# module_bga.net
KiCad netlist of a schematic drawn in EAGLE
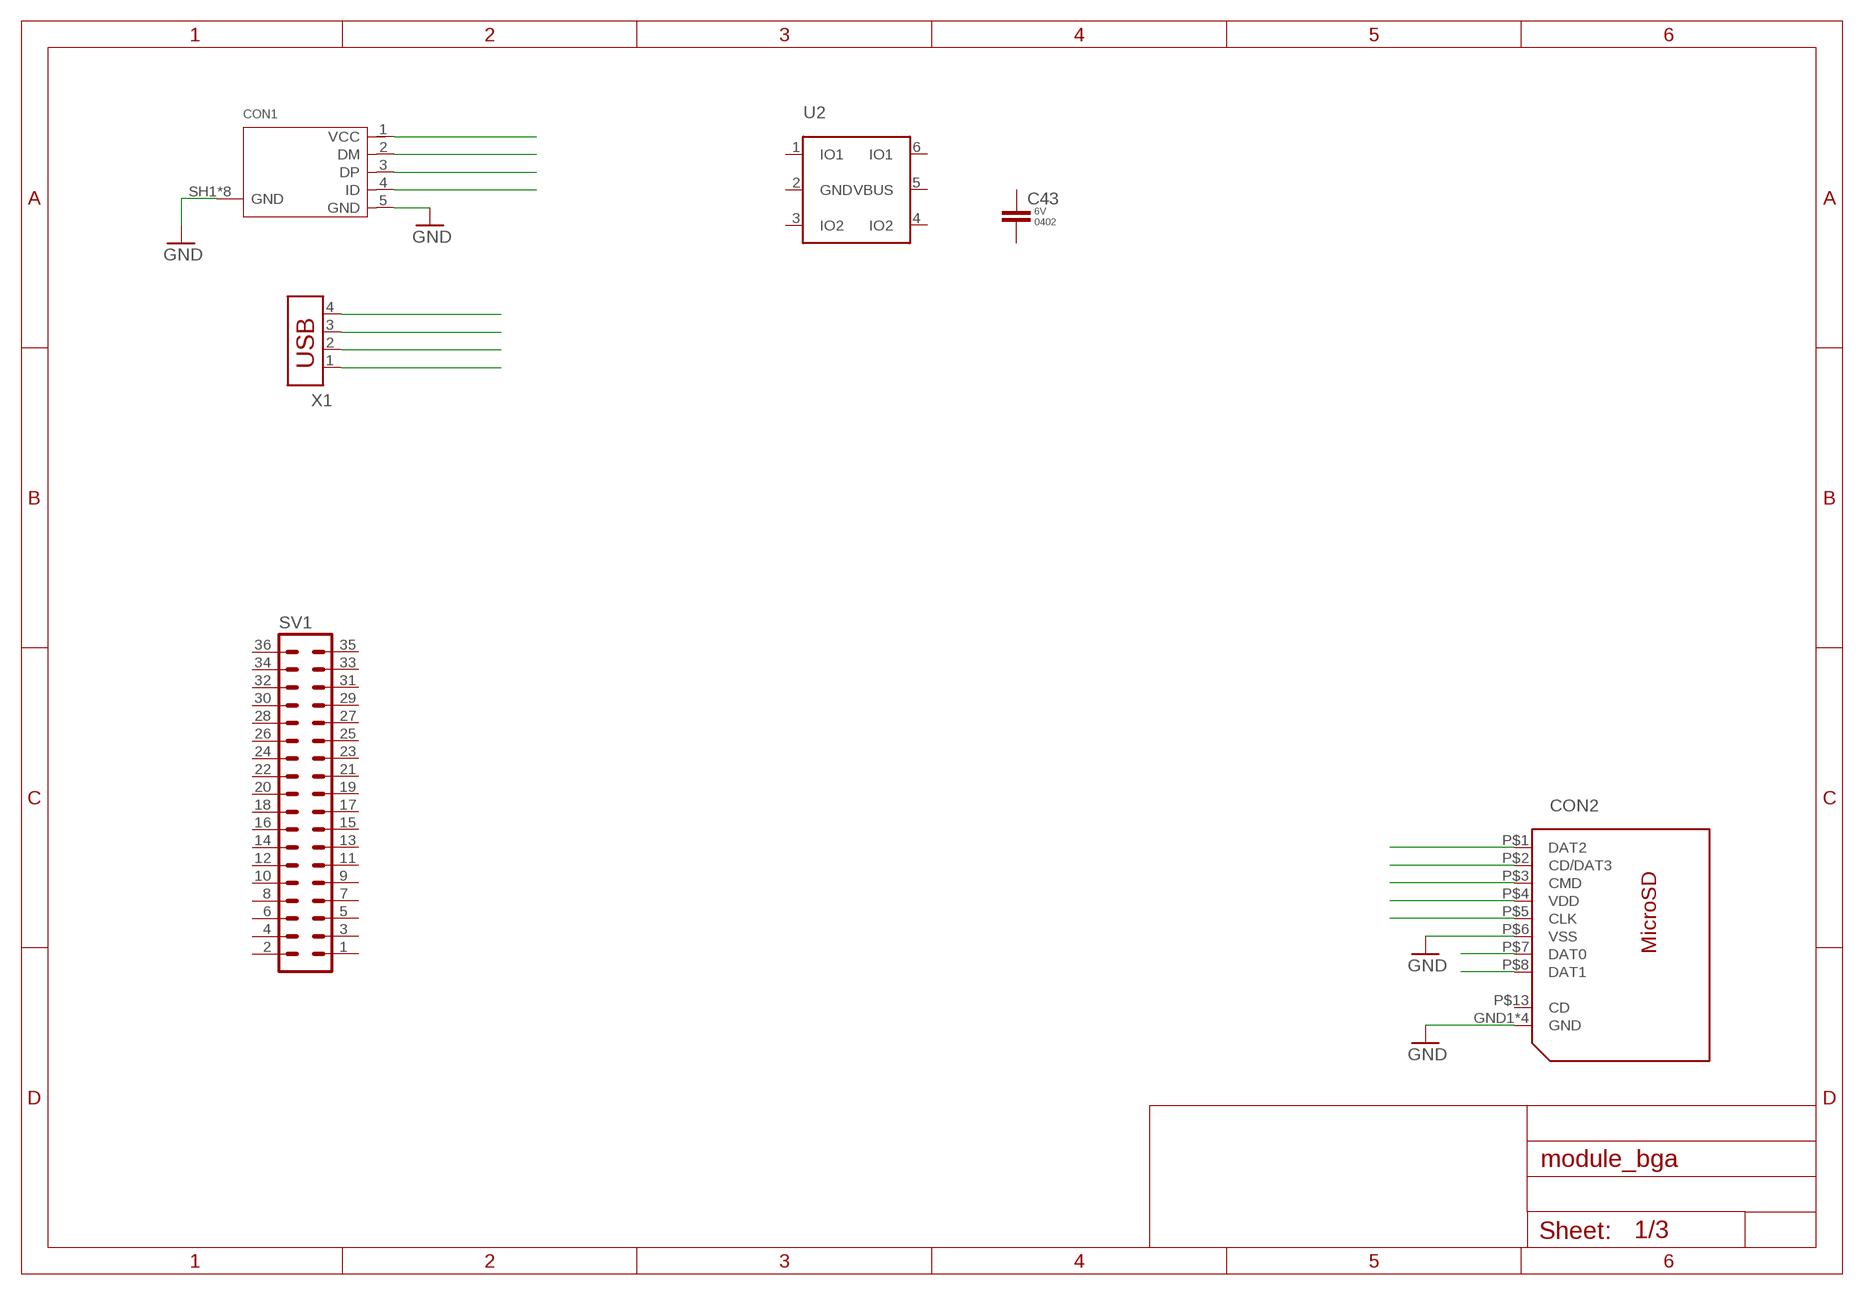
[diagram p0: schematic, sheet 1]
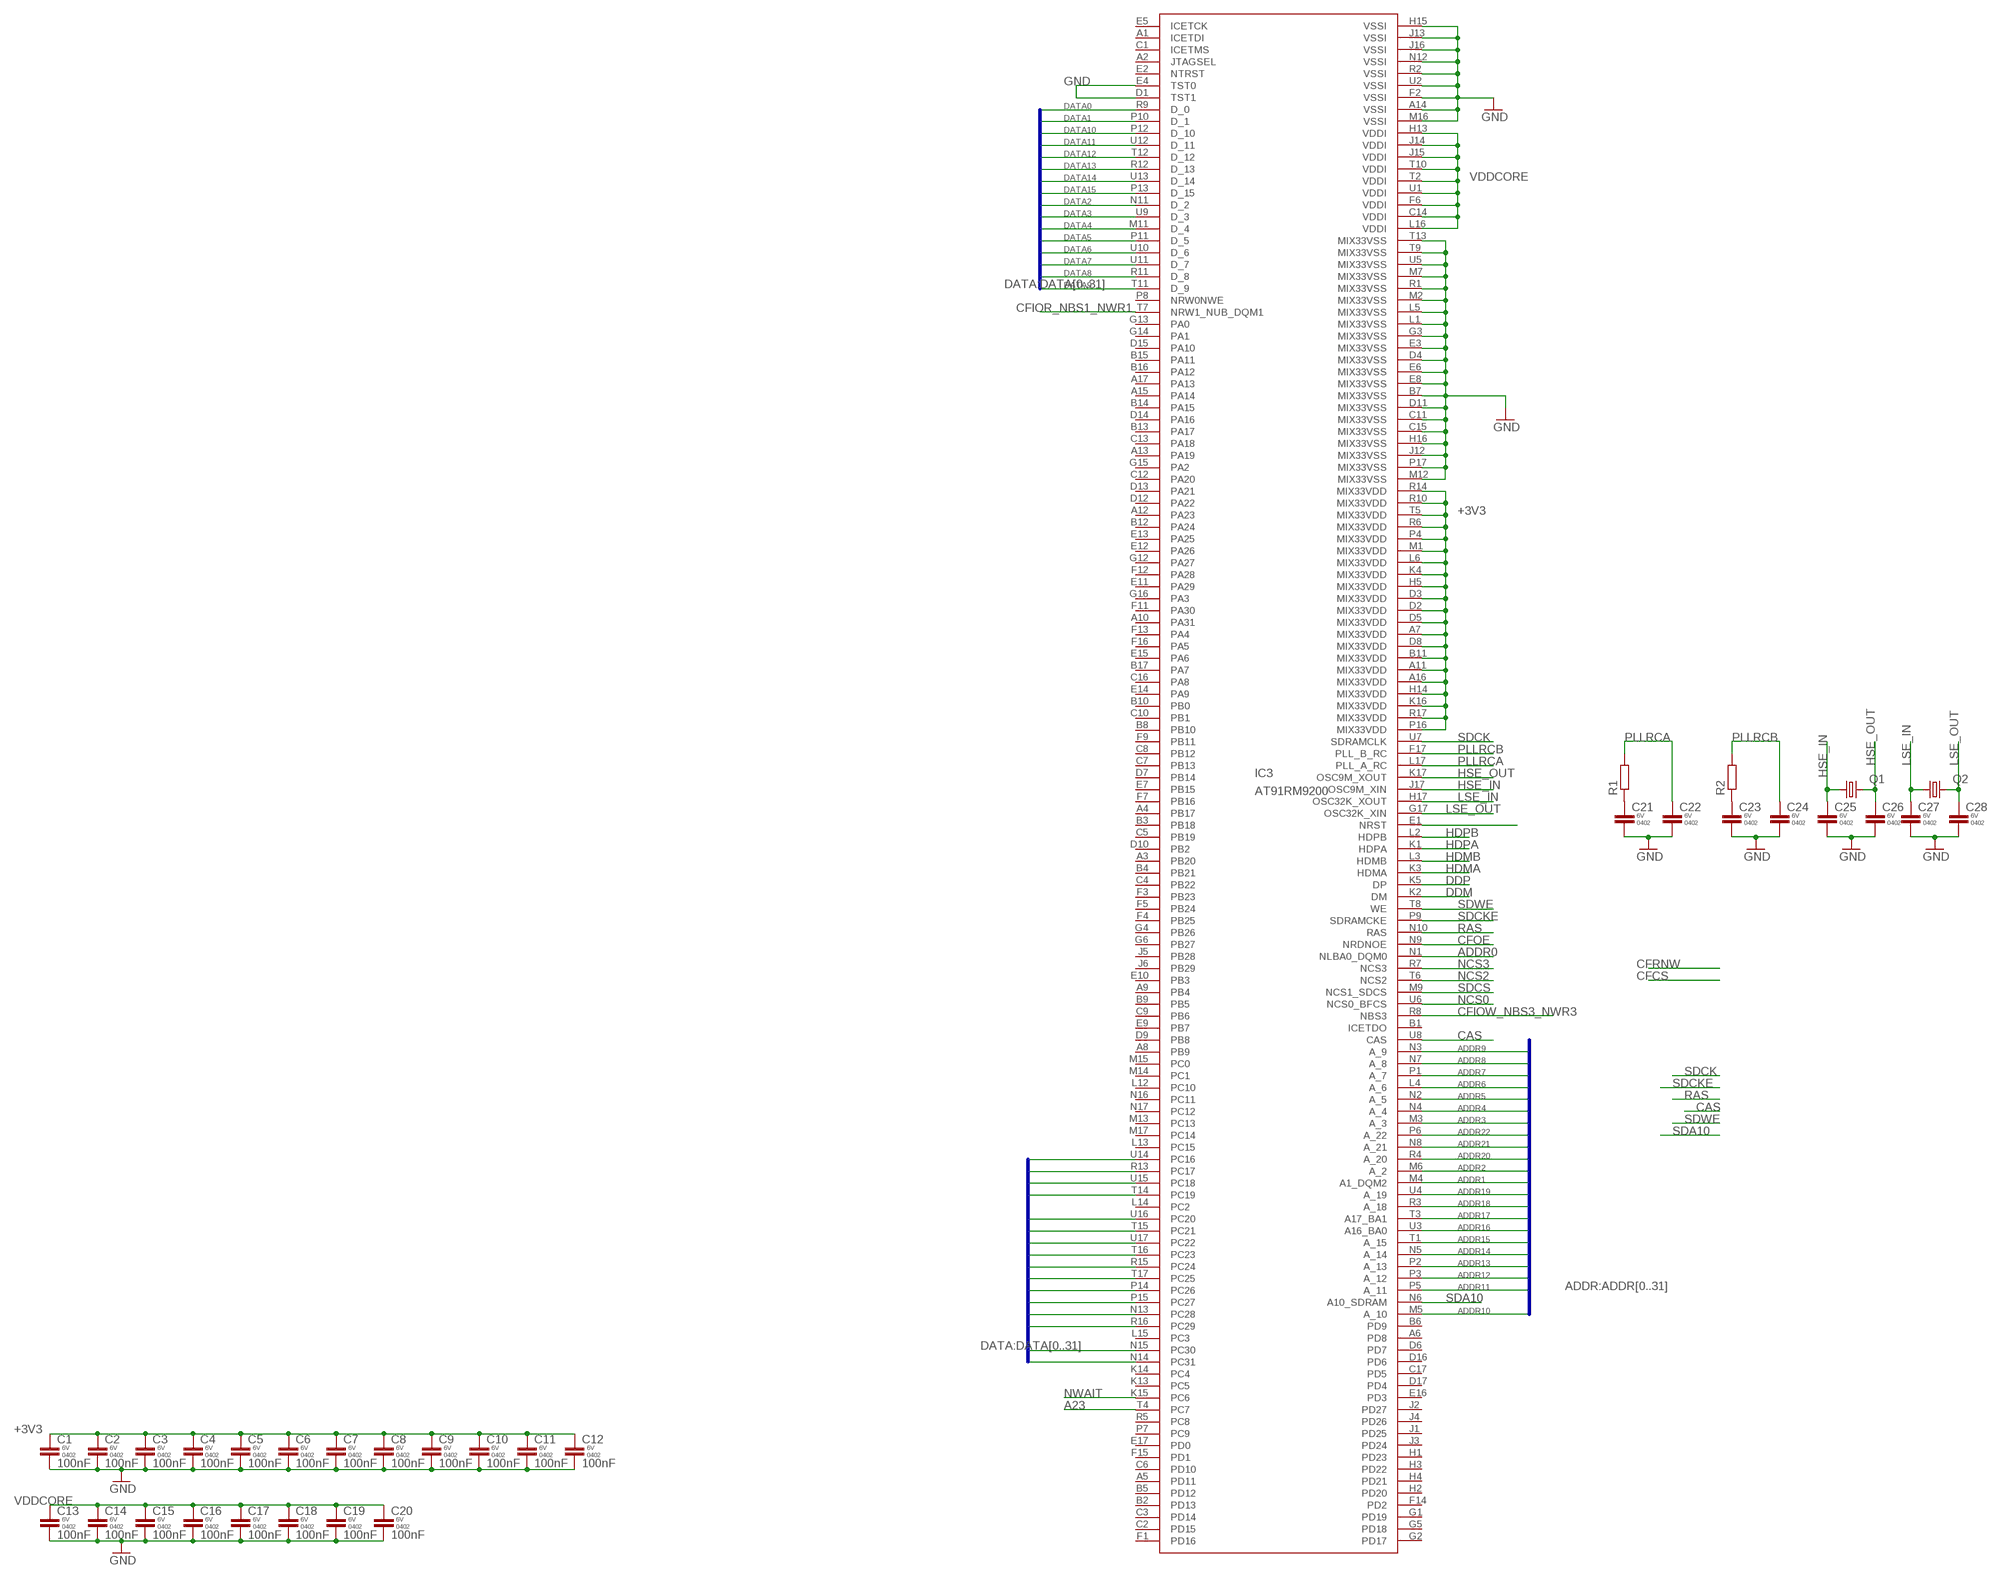
[diagram p1: schematic, sheet 2]
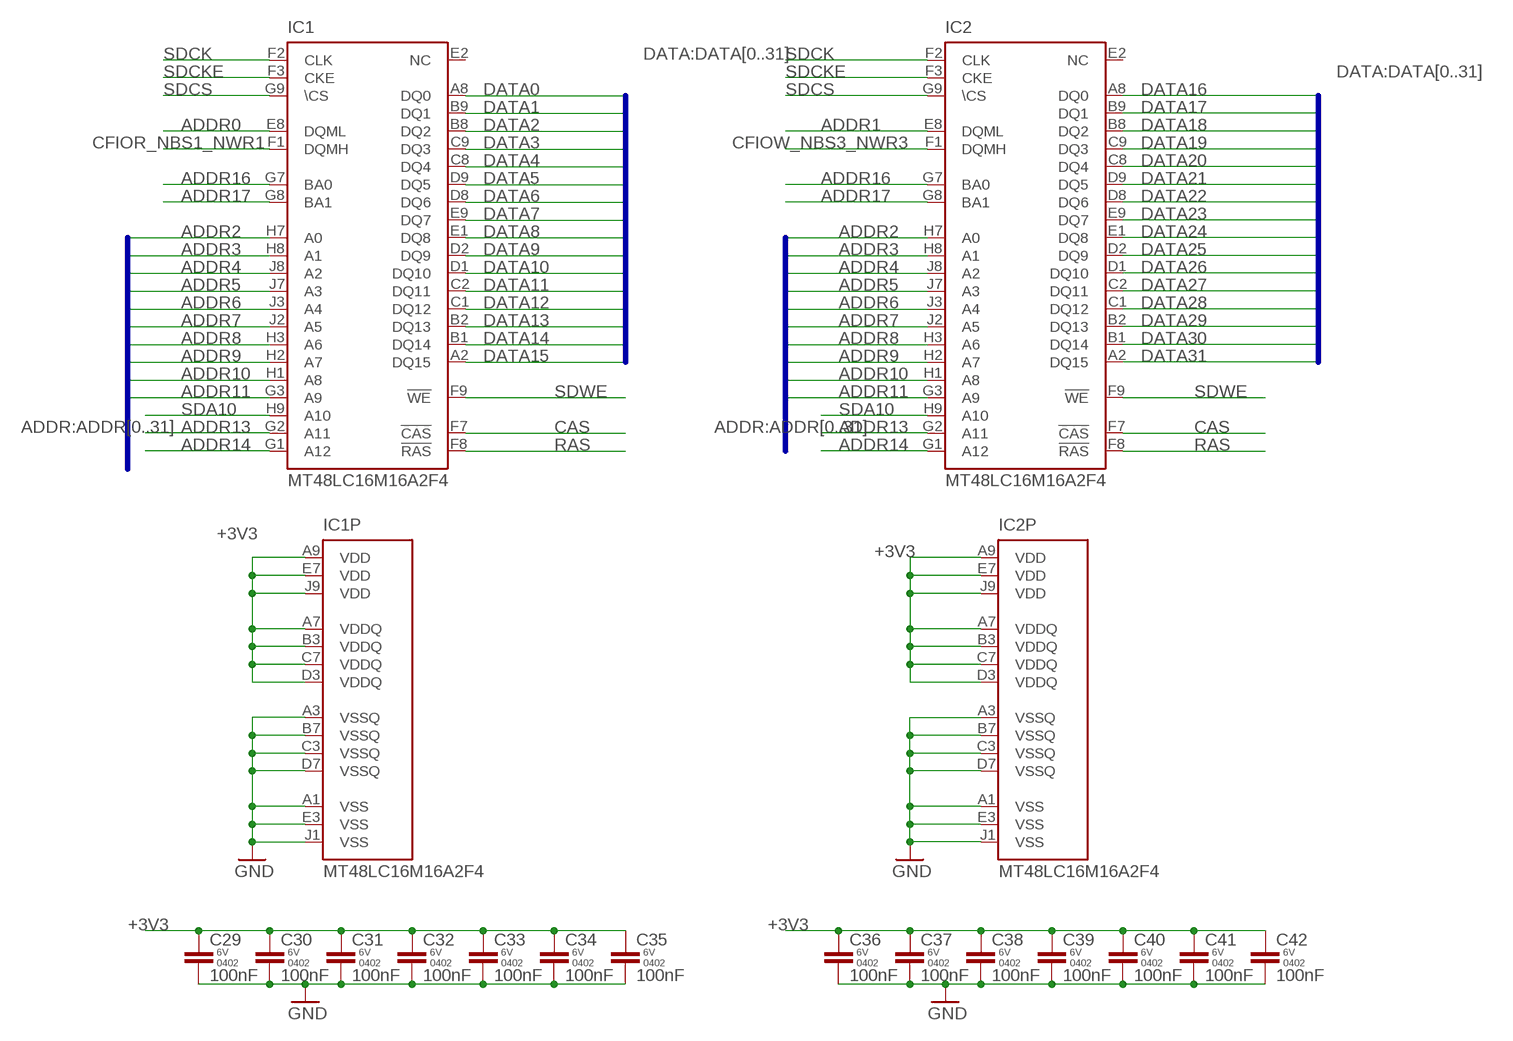
[diagram p2: schematic, sheet 3]

(export (version "E")
  (design (tool "Eeschema 10.0.6"))
  (components
    (comp (ref "C43")
      (value "CAP-0402")
      (footprint "eagle-import:C0402K")
      (fields (field (name "RATING") "6V") (field (name "PACKAGE") "0402"))
      (libsource (lib "eagle-import") (part "CAP-0402"))
    )
    (comp (ref "CON1")
      (value "10118194-0001LF")
      (footprint "eagle-import:10118194")
      (libsource (lib "eagle-import") (part "10118194-0001LF"))
    )
    (comp (ref "CON2")
      (value "112J-TXAR")
      (footprint "eagle-import:112J")
      (libsource (lib "eagle-import") (part "112J-TXAR"))
    )
    (comp (ref "SV1")
      (value "MA18-2")
      (footprint "eagle-import:MA18-2")
      (libsource (lib "eagle-import") (part "MA18-2"))
    )
    (comp (ref "U2")
      (value "USBLC6-2SC6")
      (footprint "eagle-import:SOT95P280X110-6")
      (libsource (lib "eagle-import") (part "USBLC6-2SC6"))
    )
    (comp (ref "X1")
      (value "USB-787616")
      (footprint "eagle-import:USB")
      (libsource (lib "eagle-import") (part "USB-787616"))
    )
    (comp (ref "C1")
      (value "100nF")
      (footprint "eagle-import:C0402K")
      (fields (field (name "RATING") "6V") (field (name "PACKAGE") "0402"))
      (libsource (lib "eagle-import") (part "CAP-0402"))
    )
    (comp (ref "C2")
      (value "100nF")
      (footprint "eagle-import:C0402K")
      (fields (field (name "RATING") "6V") (field (name "PACKAGE") "0402"))
      (libsource (lib "eagle-import") (part "CAP-0402"))
    )
    (comp (ref "C3")
      (value "100nF")
      (footprint "eagle-import:C0402K")
      (fields (field (name "RATING") "6V") (field (name "PACKAGE") "0402"))
      (libsource (lib "eagle-import") (part "CAP-0402"))
    )
    (comp (ref "C4")
      (value "100nF")
      (footprint "eagle-import:C0402K")
      (fields (field (name "RATING") "6V") (field (name "PACKAGE") "0402"))
      (libsource (lib "eagle-import") (part "CAP-0402"))
    )
    (comp (ref "C5")
      (value "100nF")
      (footprint "eagle-import:C0402K")
      (fields (field (name "RATING") "6V") (field (name "PACKAGE") "0402"))
      (libsource (lib "eagle-import") (part "CAP-0402"))
    )
    (comp (ref "C6")
      (value "100nF")
      (footprint "eagle-import:C0402K")
      (fields (field (name "RATING") "6V") (field (name "PACKAGE") "0402"))
      (libsource (lib "eagle-import") (part "CAP-0402"))
    )
    (comp (ref "C7")
      (value "100nF")
      (footprint "eagle-import:C0402K")
      (fields (field (name "RATING") "6V") (field (name "PACKAGE") "0402"))
      (libsource (lib "eagle-import") (part "CAP-0402"))
    )
    (comp (ref "C8")
      (value "100nF")
      (footprint "eagle-import:C0402K")
      (fields (field (name "RATING") "6V") (field (name "PACKAGE") "0402"))
      (libsource (lib "eagle-import") (part "CAP-0402"))
    )
    (comp (ref "C9")
      (value "100nF")
      (footprint "eagle-import:C0402K")
      (fields (field (name "RATING") "6V") (field (name "PACKAGE") "0402"))
      (libsource (lib "eagle-import") (part "CAP-0402"))
    )
    (comp (ref "C10")
      (value "100nF")
      (footprint "eagle-import:C0402K")
      (fields (field (name "RATING") "6V") (field (name "PACKAGE") "0402"))
      (libsource (lib "eagle-import") (part "CAP-0402"))
    )
    (comp (ref "C11")
      (value "100nF")
      (footprint "eagle-import:C0402K")
      (fields (field (name "RATING") "6V") (field (name "PACKAGE") "0402"))
      (libsource (lib "eagle-import") (part "CAP-0402"))
    )
    (comp (ref "C12")
      (value "100nF")
      (footprint "eagle-import:C0402K")
      (fields (field (name "RATING") "6V") (field (name "PACKAGE") "0402"))
      (libsource (lib "eagle-import") (part "CAP-0402"))
    )
    (comp (ref "C13")
      (value "100nF")
      (footprint "eagle-import:C0402K")
      (fields (field (name "RATING") "6V") (field (name "PACKAGE") "0402"))
      (libsource (lib "eagle-import") (part "CAP-0402"))
    )
    (comp (ref "C14")
      (value "100nF")
      (footprint "eagle-import:C0402K")
      (fields (field (name "RATING") "6V") (field (name "PACKAGE") "0402"))
      (libsource (lib "eagle-import") (part "CAP-0402"))
    )
    (comp (ref "C15")
      (value "100nF")
      (footprint "eagle-import:C0402K")
      (fields (field (name "RATING") "6V") (field (name "PACKAGE") "0402"))
      (libsource (lib "eagle-import") (part "CAP-0402"))
    )
    (comp (ref "C16")
      (value "100nF")
      (footprint "eagle-import:C0402K")
      (fields (field (name "RATING") "6V") (field (name "PACKAGE") "0402"))
      (libsource (lib "eagle-import") (part "CAP-0402"))
    )
    (comp (ref "C17")
      (value "100nF")
      (footprint "eagle-import:C0402K")
      (fields (field (name "RATING") "6V") (field (name "PACKAGE") "0402"))
      (libsource (lib "eagle-import") (part "CAP-0402"))
    )
    (comp (ref "C18")
      (value "100nF")
      (footprint "eagle-import:C0402K")
      (fields (field (name "RATING") "6V") (field (name "PACKAGE") "0402"))
      (libsource (lib "eagle-import") (part "CAP-0402"))
    )
    (comp (ref "C19")
      (value "100nF")
      (footprint "eagle-import:C0402K")
      (fields (field (name "RATING") "6V") (field (name "PACKAGE") "0402"))
      (libsource (lib "eagle-import") (part "CAP-0402"))
    )
    (comp (ref "C20")
      (value "100nF")
      (footprint "eagle-import:C0402K")
      (fields (field (name "RATING") "6V") (field (name "PACKAGE") "0402"))
      (libsource (lib "eagle-import") (part "CAP-0402"))
    )
    (comp (ref "C21")
      (value "CAP-0402")
      (footprint "eagle-import:C0402K")
      (fields (field (name "RATING") "6V") (field (name "PACKAGE") "0402"))
      (libsource (lib "eagle-import") (part "CAP-0402"))
    )
    (comp (ref "C22")
      (value "CAP-0402")
      (footprint "eagle-import:C0402K")
      (fields (field (name "RATING") "6V") (field (name "PACKAGE") "0402"))
      (libsource (lib "eagle-import") (part "CAP-0402"))
    )
    (comp (ref "C23")
      (value "CAP-0402")
      (footprint "eagle-import:C0402K")
      (fields (field (name "RATING") "6V") (field (name "PACKAGE") "0402"))
      (libsource (lib "eagle-import") (part "CAP-0402"))
    )
    (comp (ref "C24")
      (value "CAP-0402")
      (footprint "eagle-import:C0402K")
      (fields (field (name "RATING") "6V") (field (name "PACKAGE") "0402"))
      (libsource (lib "eagle-import") (part "CAP-0402"))
    )
    (comp (ref "C25")
      (value "CAP-0402")
      (footprint "eagle-import:C0402K")
      (fields (field (name "RATING") "6V") (field (name "PACKAGE") "0402"))
      (libsource (lib "eagle-import") (part "CAP-0402"))
    )
    (comp (ref "C26")
      (value "CAP-0402")
      (footprint "eagle-import:C0402K")
      (fields (field (name "RATING") "6V") (field (name "PACKAGE") "0402"))
      (libsource (lib "eagle-import") (part "CAP-0402"))
    )
    (comp (ref "C27")
      (value "CAP-0402")
      (footprint "eagle-import:C0402K")
      (fields (field (name "RATING") "6V") (field (name "PACKAGE") "0402"))
      (libsource (lib "eagle-import") (part "CAP-0402"))
    )
    (comp (ref "C28")
      (value "CAP-0402")
      (footprint "eagle-import:C0402K")
      (fields (field (name "RATING") "6V") (field (name "PACKAGE") "0402"))
      (libsource (lib "eagle-import") (part "CAP-0402"))
    )
    (comp (ref "IC3")
      (value "AT91RM9200")
      (footprint "eagle-import:LFBGA256_A_291X326")
      (fields (field (name "MPN") "AT91RM9200-EK"))
      (libsource (lib "eagle-import") (part "AT91RM9200"))
    )
    (comp (ref "Q1")
      (value "KX-7")
      (footprint "eagle-import:3.2X2.5_KX-7")
      (libsource (lib "eagle-import") (part "KX-7"))
    )
    (comp (ref "Q2")
      (value "KX-327-NHF")
      (footprint "eagle-import:3.2X1.5")
      (libsource (lib "eagle-import") (part "KX-327-NHF"))
    )
    (comp (ref "R1")
      (value "R-EU_R0402")
      (footprint "eagle-import:R0402")
      (libsource (lib "eagle-import") (part "R-EU_R0402"))
    )
    (comp (ref "R2")
      (value "R-EU_R0402")
      (footprint "eagle-import:R0402")
      (libsource (lib "eagle-import") (part "R-EU_R0402"))
    )
    (comp (ref "C29")
      (value "100nF")
      (footprint "eagle-import:C0402K")
      (fields (field (name "RATING") "6V") (field (name "PACKAGE") "0402"))
      (libsource (lib "eagle-import") (part "CAP-0402"))
    )
    (comp (ref "C30")
      (value "100nF")
      (footprint "eagle-import:C0402K")
      (fields (field (name "RATING") "6V") (field (name "PACKAGE") "0402"))
      (libsource (lib "eagle-import") (part "CAP-0402"))
    )
    (comp (ref "C31")
      (value "100nF")
      (footprint "eagle-import:C0402K")
      (fields (field (name "RATING") "6V") (field (name "PACKAGE") "0402"))
      (libsource (lib "eagle-import") (part "CAP-0402"))
    )
    (comp (ref "C32")
      (value "100nF")
      (footprint "eagle-import:C0402K")
      (fields (field (name "RATING") "6V") (field (name "PACKAGE") "0402"))
      (libsource (lib "eagle-import") (part "CAP-0402"))
    )
    (comp (ref "C33")
      (value "100nF")
      (footprint "eagle-import:C0402K")
      (fields (field (name "RATING") "6V") (field (name "PACKAGE") "0402"))
      (libsource (lib "eagle-import") (part "CAP-0402"))
    )
    (comp (ref "C34")
      (value "100nF")
      (footprint "eagle-import:C0402K")
      (fields (field (name "RATING") "6V") (field (name "PACKAGE") "0402"))
      (libsource (lib "eagle-import") (part "CAP-0402"))
    )
    (comp (ref "C35")
      (value "100nF")
      (footprint "eagle-import:C0402K")
      (fields (field (name "RATING") "6V") (field (name "PACKAGE") "0402"))
      (libsource (lib "eagle-import") (part "CAP-0402"))
    )
    (comp (ref "C36")
      (value "100nF")
      (footprint "eagle-import:C0402K")
      (fields (field (name "RATING") "6V") (field (name "PACKAGE") "0402"))
      (libsource (lib "eagle-import") (part "CAP-0402"))
    )
    (comp (ref "C37")
      (value "100nF")
      (footprint "eagle-import:C0402K")
      (fields (field (name "RATING") "6V") (field (name "PACKAGE") "0402"))
      (libsource (lib "eagle-import") (part "CAP-0402"))
    )
    (comp (ref "C38")
      (value "100nF")
      (footprint "eagle-import:C0402K")
      (fields (field (name "RATING") "6V") (field (name "PACKAGE") "0402"))
      (libsource (lib "eagle-import") (part "CAP-0402"))
    )
    (comp (ref "C39")
      (value "100nF")
      (footprint "eagle-import:C0402K")
      (fields (field (name "RATING") "6V") (field (name "PACKAGE") "0402"))
      (libsource (lib "eagle-import") (part "CAP-0402"))
    )
    (comp (ref "C40")
      (value "100nF")
      (footprint "eagle-import:C0402K")
      (fields (field (name "RATING") "6V") (field (name "PACKAGE") "0402"))
      (libsource (lib "eagle-import") (part "CAP-0402"))
    )
    (comp (ref "C41")
      (value "100nF")
      (footprint "eagle-import:C0402K")
      (fields (field (name "RATING") "6V") (field (name "PACKAGE") "0402"))
      (libsource (lib "eagle-import") (part "CAP-0402"))
    )
    (comp (ref "C42")
      (value "100nF")
      (footprint "eagle-import:C0402K")
      (fields (field (name "RATING") "6V") (field (name "PACKAGE") "0402"))
      (libsource (lib "eagle-import") (part "CAP-0402"))
    )
    (comp (ref "IC1")
      (value "MT48LC16M16A2F4")
      (footprint "eagle-import:BGA81C80P9X9_800X800X100")
      (libsource (lib "eagle-import") (part "MT48LC16M16A2F4"))
    )
    (comp (ref "IC2")
      (value "MT48LC16M16A2F4")
      (footprint "eagle-import:BGA81C80P9X9_800X800X100")
      (libsource (lib "eagle-import") (part "MT48LC16M16A2F4"))
    )
  )
  (nets
    (net (code "129") (name "+3V3") (class "Default")
      (node (ref "C1") (pin "1") (pinfunction "1_1") (pintype "passive"))
      (node (ref "C10") (pin "1") (pinfunction "1_1") (pintype "passive"))
      (node (ref "C11") (pin "1") (pinfunction "1_1") (pintype "passive"))
      (node (ref "C12") (pin "1") (pinfunction "1_1") (pintype "passive"))
      (node (ref "C2") (pin "1") (pinfunction "1_1") (pintype "passive"))
      (node (ref "C29") (pin "1") (pinfunction "1_1") (pintype "passive"))
      (node (ref "C3") (pin "1") (pinfunction "1_1") (pintype "passive"))
      (node (ref "C30") (pin "1") (pinfunction "1_1") (pintype "passive"))
      (node (ref "C31") (pin "1") (pinfunction "1_1") (pintype "passive"))
      (node (ref "C32") (pin "1") (pinfunction "1_1") (pintype "passive"))
      (node (ref "C33") (pin "1") (pinfunction "1_1") (pintype "passive"))
      (node (ref "C34") (pin "1") (pinfunction "1_1") (pintype "passive"))
      (node (ref "C35") (pin "1") (pinfunction "1_1") (pintype "passive"))
      (node (ref "C36") (pin "1") (pinfunction "1_1") (pintype "passive"))
      (node (ref "C37") (pin "1") (pinfunction "1_1") (pintype "passive"))
      (node (ref "C38") (pin "1") (pinfunction "1_1") (pintype "passive"))
      (node (ref "C39") (pin "1") (pinfunction "1_1") (pintype "passive"))
      (node (ref "C4") (pin "1") (pinfunction "1_1") (pintype "passive"))
      (node (ref "C40") (pin "1") (pinfunction "1_1") (pintype "passive"))
      (node (ref "C41") (pin "1") (pinfunction "1_1") (pintype "passive"))
      (node (ref "C42") (pin "1") (pinfunction "1_1") (pintype "passive"))
      (node (ref "C5") (pin "1") (pinfunction "1_1") (pintype "passive"))
      (node (ref "C6") (pin "1") (pinfunction "1_1") (pintype "passive"))
      (node (ref "C7") (pin "1") (pinfunction "1_1") (pintype "passive"))
      (node (ref "C8") (pin "1") (pinfunction "1_1") (pintype "passive"))
      (node (ref "C9") (pin "1") (pinfunction "1_1") (pintype "passive"))
      (node (ref "IC1") (pin "A7") (pinfunction "VDDQ_A7") (pintype "power_in"))
      (node (ref "IC1") (pin "A9") (pinfunction "VDD_A9") (pintype "power_in"))
      (node (ref "IC1") (pin "B3") (pinfunction "VDDQ_B3") (pintype "power_in"))
      (node (ref "IC1") (pin "C7") (pinfunction "VDDQ_C7") (pintype "power_in"))
      (node (ref "IC1") (pin "D3") (pinfunction "VDDQ_D3") (pintype "power_in"))
      (node (ref "IC1") (pin "E7") (pinfunction "VDD_E7") (pintype "power_in"))
      (node (ref "IC1") (pin "J9") (pinfunction "VDD_J9") (pintype "power_in"))
      (node (ref "IC2") (pin "A7") (pinfunction "VDDQ_A7") (pintype "power_in"))
      (node (ref "IC2") (pin "A9") (pinfunction "VDD_A9") (pintype "power_in"))
      (node (ref "IC2") (pin "B3") (pinfunction "VDDQ_B3") (pintype "power_in"))
      (node (ref "IC2") (pin "C7") (pinfunction "VDDQ_C7") (pintype "power_in"))
      (node (ref "IC2") (pin "D3") (pinfunction "VDDQ_D3") (pintype "power_in"))
      (node (ref "IC2") (pin "E7") (pinfunction "VDD_E7") (pintype "power_in"))
      (node (ref "IC2") (pin "J9") (pinfunction "VDD_J9") (pintype "power_in"))
      (node (ref "IC3") (pin "A11") (pinfunction "MIX33VDD_A11") (pintype "power_in"))
      (node (ref "IC3") (pin "A16") (pinfunction "MIX33VDD_A16") (pintype "power_in"))
      (node (ref "IC3") (pin "A7") (pinfunction "MIX33VDD_A7") (pintype "power_in"))
      (node (ref "IC3") (pin "B11") (pinfunction "MIX33VDD_B11") (pintype "power_in"))
      (node (ref "IC3") (pin "D2") (pinfunction "MIX33VDD_D2") (pintype "power_in"))
      (node (ref "IC3") (pin "D3") (pinfunction "MIX33VDD_D3") (pintype "power_in"))
      (node (ref "IC3") (pin "D5") (pinfunction "MIX33VDD_D5") (pintype "power_in"))
      (node (ref "IC3") (pin "D8") (pinfunction "MIX33VDD_D8") (pintype "power_in"))
      (node (ref "IC3") (pin "H14") (pinfunction "MIX33VDD_H14") (pintype "power_in"))
      (node (ref "IC3") (pin "H5") (pinfunction "MIX33VDD_H5") (pintype "power_in"))
      (node (ref "IC3") (pin "K16") (pinfunction "MIX33VDD_K16") (pintype "power_in"))
      (node (ref "IC3") (pin "K4") (pinfunction "MIX33VDD_K4") (pintype "power_in"))
      (node (ref "IC3") (pin "L6") (pinfunction "MIX33VDD_L6") (pintype "power_in"))
      (node (ref "IC3") (pin "M1") (pinfunction "MIX33VDD_M1") (pintype "power_in"))
      (node (ref "IC3") (pin "P16") (pinfunction "MIX33VDD_P16") (pintype "power_in"))
      (node (ref "IC3") (pin "P4") (pinfunction "MIX33VDD_P4") (pintype "power_in"))
      (node (ref "IC3") (pin "R10") (pinfunction "MIX33VDD_R10") (pintype "power_in"))
      (node (ref "IC3") (pin "R14") (pinfunction "MIX33VDD_R14") (pintype "power_in"))
      (node (ref "IC3") (pin "R17") (pinfunction "MIX33VDD_R17") (pintype "power_in"))
      (node (ref "IC3") (pin "R6") (pinfunction "MIX33VDD_R6") (pintype "power_in"))
      (node (ref "IC3") (pin "T5") (pinfunction "MIX33VDD_T5") (pintype "power_in"))
    )
    (net (code "134") (name "A23") (class "Default")
      (node (ref "IC3") (pin "T4") (pinfunction "PC7_T4") (pintype "bidirectional"))
    )
    (net (code "135") (name "ADDR0") (class "Default")
      (node (ref "IC1") (pin "E8") (pinfunction "DQML_E8") (pintype "input"))
      (node (ref "IC3") (pin "N1") (pinfunction "NLBA0_DQM0_N1") (pintype "output"))
    )
    (net (code "136") (name "ADDR1") (class "Default")
      (node (ref "IC2") (pin "E8") (pinfunction "DQML_E8") (pintype "input"))
      (node (ref "IC3") (pin "M4") (pinfunction "A1_DQM2_M4") (pintype "output"))
    )
    (net (code "137") (name "ADDR2") (class "Default")
      (node (ref "IC1") (pin "H7") (pinfunction "A0_H7") (pintype "input"))
      (node (ref "IC2") (pin "H7") (pinfunction "A0_H7") (pintype "input"))
      (node (ref "IC3") (pin "M6") (pinfunction "A_2_M6") (pintype "output"))
    )
    (net (code "138") (name "ADDR3") (class "Default")
      (node (ref "IC1") (pin "H8") (pinfunction "A1_H8") (pintype "input"))
      (node (ref "IC2") (pin "H8") (pinfunction "A1_H8") (pintype "input"))
      (node (ref "IC3") (pin "M3") (pinfunction "A_3_M3") (pintype "output"))
    )
    (net (code "139") (name "ADDR4") (class "Default")
      (node (ref "IC1") (pin "J8") (pinfunction "A2_J8") (pintype "input"))
      (node (ref "IC2") (pin "J8") (pinfunction "A2_J8") (pintype "input"))
      (node (ref "IC3") (pin "N4") (pinfunction "A_4_N4") (pintype "output"))
    )
    (net (code "140") (name "ADDR5") (class "Default")
      (node (ref "IC1") (pin "J7") (pinfunction "A3_J7") (pintype "input"))
      (node (ref "IC2") (pin "J7") (pinfunction "A3_J7") (pintype "input"))
      (node (ref "IC3") (pin "N2") (pinfunction "A_5_N2") (pintype "output"))
    )
    (net (code "141") (name "ADDR6") (class "Default")
      (node (ref "IC1") (pin "J3") (pinfunction "A4_J3") (pintype "input"))
      (node (ref "IC2") (pin "J3") (pinfunction "A4_J3") (pintype "input"))
      (node (ref "IC3") (pin "L4") (pinfunction "A_6_L4") (pintype "output"))
    )
    (net (code "142") (name "ADDR7") (class "Default")
      (node (ref "IC1") (pin "J2") (pinfunction "A5_J2") (pintype "input"))
      (node (ref "IC2") (pin "J2") (pinfunction "A5_J2") (pintype "input"))
      (node (ref "IC3") (pin "P1") (pinfunction "A_7_P1") (pintype "output"))
    )
    (net (code "143") (name "ADDR8") (class "Default")
      (node (ref "IC1") (pin "H3") (pinfunction "A6_H3") (pintype "input"))
      (node (ref "IC2") (pin "H3") (pinfunction "A6_H3") (pintype "input"))
      (node (ref "IC3") (pin "N7") (pinfunction "A_8_N7") (pintype "output"))
    )
    (net (code "144") (name "ADDR9") (class "Default")
      (node (ref "IC1") (pin "H2") (pinfunction "A7_H2") (pintype "input"))
      (node (ref "IC2") (pin "H2") (pinfunction "A7_H2") (pintype "input"))
      (node (ref "IC3") (pin "N3") (pinfunction "A_9_N3") (pintype "output"))
    )
    (net (code "145") (name "ADDR10") (class "Default")
      (node (ref "IC1") (pin "H1") (pinfunction "A8_H1") (pintype "input"))
      (node (ref "IC2") (pin "H1") (pinfunction "A8_H1") (pintype "input"))
      (node (ref "IC3") (pin "M5") (pinfunction "A_10_M5") (pintype "output"))
    )
    (net (code "146") (name "ADDR11") (class "Default")
      (node (ref "IC1") (pin "G3") (pinfunction "A9_G3") (pintype "input"))
      (node (ref "IC2") (pin "G3") (pinfunction "A9_G3") (pintype "input"))
      (node (ref "IC3") (pin "P5") (pinfunction "A_11_P5") (pintype "output"))
    )
    (net (code "147") (name "ADDR12") (class "Default")
      (node (ref "IC3") (pin "P3") (pinfunction "A_12_P3") (pintype "output"))
    )
    (net (code "148") (name "ADDR13") (class "Default")
      (node (ref "IC1") (pin "G2") (pinfunction "A11_G2") (pintype "input"))
      (node (ref "IC2") (pin "G2") (pinfunction "A11_G2") (pintype "input"))
      (node (ref "IC3") (pin "P2") (pinfunction "A_13_P2") (pintype "output"))
    )
    (net (code "149") (name "ADDR14") (class "Default")
      (node (ref "IC1") (pin "G1") (pinfunction "A12_G1") (pintype "input"))
      (node (ref "IC2") (pin "G1") (pinfunction "A12_G1") (pintype "input"))
      (node (ref "IC3") (pin "N5") (pinfunction "A_14_N5") (pintype "output"))
    )
    (net (code "150") (name "ADDR15") (class "Default")
      (node (ref "IC3") (pin "T1") (pinfunction "A_15_T1") (pintype "output"))
    )
    (net (code "151") (name "ADDR16") (class "Default")
      (node (ref "IC1") (pin "G7") (pinfunction "BA0_G7") (pintype "input"))
      (node (ref "IC2") (pin "G7") (pinfunction "BA0_G7") (pintype "input"))
      (node (ref "IC3") (pin "U3") (pinfunction "A16_BA0_U3") (pintype "output"))
    )
    (net (code "152") (name "ADDR17") (class "Default")
      (node (ref "IC1") (pin "G8") (pinfunction "BA1_G8") (pintype "input"))
      (node (ref "IC2") (pin "G8") (pinfunction "BA1_G8") (pintype "input"))
      (node (ref "IC3") (pin "T3") (pinfunction "A17_BA1_T3") (pintype "output"))
    )
    (net (code "153") (name "ADDR18") (class "Default")
      (node (ref "IC3") (pin "R3") (pinfunction "A_18_R3") (pintype "output"))
    )
    (net (code "154") (name "ADDR19") (class "Default")
      (node (ref "IC3") (pin "U4") (pinfunction "A_19_U4") (pintype "output"))
    )
    (net (code "155") (name "ADDR20") (class "Default")
      (node (ref "IC3") (pin "R4") (pinfunction "A_20_R4") (pintype "output"))
    )
    (net (code "156") (name "ADDR21") (class "Default")
      (node (ref "IC3") (pin "N8") (pinfunction "A_21_N8") (pintype "output"))
    )
    (net (code "157") (name "ADDR22") (class "Default")
      (node (ref "IC3") (pin "P6") (pinfunction "A_22_P6") (pintype "output"))
    )
    (net (code "158") (name "CAS") (class "Default")
      (node (ref "IC1") (pin "F7") (pinfunction "~{CAS}_F7") (pintype "input"))
      (node (ref "IC2") (pin "F7") (pinfunction "~{CAS}_F7") (pintype "input"))
      (node (ref "IC3") (pin "U8") (pinfunction "CAS_U8") (pintype "output"))
    )
    (net (code "159") (name "CD") (class "Default")
      (node (ref "CON2") (pin "P$13") (pinfunction "CD_P$13") (pintype "power_in"))
    )
    (net (code "161") (name "CFIOR_NBS1_NWR1") (class "Default")
      (node (ref "IC1") (pin "F1") (pinfunction "DQMH_F1") (pintype "input"))
      (node (ref "IC3") (pin "T7") (pinfunction "NRW1_NUB_DQM1_T7") (pintype "bidirectional"))
    )
    (net (code "162") (name "CFIOW_NBS3_NWR3") (class "Default")
      (node (ref "IC2") (pin "F1") (pinfunction "DQMH_F1") (pintype "input"))
      (node (ref "IC3") (pin "R8") (pinfunction "NBS3_R8") (pintype "output"))
    )
    (net (code "163") (name "CFOE") (class "Default")
      (node (ref "IC3") (pin "N9") (pinfunction "NRDNOE_N9") (pintype "output"))
    )
    (net (code "165") (name "DATA0") (class "Default")
      (node (ref "IC1") (pin "A8") (pinfunction "DQ0_A8") (pintype "tri_state"))
      (node (ref "IC3") (pin "R9") (pinfunction "D_0_R9") (pintype "bidirectional"))
    )
    (net (code "166") (name "DATA1") (class "Default")
      (node (ref "IC1") (pin "B9") (pinfunction "DQ1_B9") (pintype "tri_state"))
      (node (ref "IC3") (pin "P10") (pinfunction "D_1_P10") (pintype "bidirectional"))
    )
    (net (code "167") (name "DATA2") (class "Default")
      (node (ref "IC1") (pin "B8") (pinfunction "DQ2_B8") (pintype "tri_state"))
      (node (ref "IC3") (pin "N11") (pinfunction "D_2_N11") (pintype "bidirectional"))
    )
    (net (code "168") (name "DATA3") (class "Default")
      (node (ref "IC1") (pin "C9") (pinfunction "DQ3_C9") (pintype "tri_state"))
      (node (ref "IC3") (pin "U9") (pinfunction "D_3_U9") (pintype "bidirectional"))
    )
    (net (code "169") (name "DATA4") (class "Default")
      (node (ref "IC1") (pin "C8") (pinfunction "DQ4_C8") (pintype "tri_state"))
      (node (ref "IC3") (pin "M11") (pinfunction "D_4_M11") (pintype "bidirectional"))
    )
    (net (code "170") (name "DATA5") (class "Default")
      (node (ref "IC1") (pin "D9") (pinfunction "DQ5_D9") (pintype "tri_state"))
      (node (ref "IC3") (pin "P11") (pinfunction "D_5_P11") (pintype "bidirectional"))
    )
    (net (code "171") (name "DATA6") (class "Default")
      (node (ref "IC1") (pin "D8") (pinfunction "DQ6_D8") (pintype "tri_state"))
      (node (ref "IC3") (pin "U10") (pinfunction "D_6_U10") (pintype "bidirectional"))
    )
    (net (code "172") (name "DATA7") (class "Default")
      (node (ref "IC1") (pin "E9") (pinfunction "DQ7_E9") (pintype "tri_state"))
      (node (ref "IC3") (pin "U11") (pinfunction "D_7_U11") (pintype "bidirectional"))
    )
    (net (code "173") (name "DATA8") (class "Default")
      (node (ref "IC1") (pin "E1") (pinfunction "DQ8_E1") (pintype "tri_state"))
      (node (ref "IC3") (pin "R11") (pinfunction "D_8_R11") (pintype "bidirectional"))
    )
    (net (code "174") (name "DATA9") (class "Default")
      (node (ref "IC1") (pin "D2") (pinfunction "DQ9_D2") (pintype "tri_state"))
      (node (ref "IC3") (pin "T11") (pinfunction "D_9_T11") (pintype "bidirectional"))
    )
    (net (code "175") (name "DATA10") (class "Default")
      (node (ref "IC1") (pin "D1") (pinfunction "DQ10_D1") (pintype "tri_state"))
      (node (ref "IC3") (pin "P12") (pinfunction "D_10_P12") (pintype "bidirectional"))
    )
    (net (code "176") (name "DATA11") (class "Default")
      (node (ref "IC1") (pin "C2") (pinfunction "DQ11_C2") (pintype "tri_state"))
      (node (ref "IC3") (pin "U12") (pinfunction "D_11_U12") (pintype "bidirectional"))
    )
    (net (code "177") (name "DATA12") (class "Default")
      (node (ref "IC1") (pin "C1") (pinfunction "DQ12_C1") (pintype "tri_state"))
      (node (ref "IC3") (pin "T12") (pinfunction "D_12_T12") (pintype "bidirectional"))
    )
    (net (code "178") (name "DATA13") (class "Default")
      (node (ref "IC1") (pin "B2") (pinfunction "DQ13_B2") (pintype "tri_state"))
      (node (ref "IC3") (pin "R12") (pinfunction "D_13_R12") (pintype "bidirectional"))
    )
    (net (code "179") (name "DATA14") (class "Default")
      (node (ref "IC1") (pin "B1") (pinfunction "DQ14_B1") (pintype "tri_state"))
      (node (ref "IC3") (pin "U13") (pinfunction "D_14_U13") (pintype "bidirectional"))
    )
    (net (code "180") (name "DATA15") (class "Default")
      (node (ref "IC1") (pin "A2") (pinfunction "DQ15_A2") (pintype "tri_state"))
      (node (ref "IC3") (pin "P13") (pinfunction "D_15_P13") (pintype "bidirectional"))
    )
    (net (code "181") (name "DATA16") (class "Default")
      (node (ref "IC2") (pin "A8") (pinfunction "DQ0_A8") (pintype "tri_state"))
      (node (ref "IC3") (pin "U14") (pinfunction "PC16_U14") (pintype "bidirectional"))
    )
    (net (code "182") (name "DATA17") (class "Default")
      (node (ref "IC2") (pin "B9") (pinfunction "DQ1_B9") (pintype "tri_state"))
      (node (ref "IC3") (pin "R13") (pinfunction "PC17_R13") (pintype "bidirectional"))
    )
    (net (code "183") (name "DATA18") (class "Default")
      (node (ref "IC2") (pin "B8") (pinfunction "DQ2_B8") (pintype "tri_state"))
      (node (ref "IC3") (pin "U15") (pinfunction "PC18_U15") (pintype "bidirectional"))
    )
    (net (code "184") (name "DATA19") (class "Default")
      (node (ref "IC2") (pin "C9") (pinfunction "DQ3_C9") (pintype "tri_state"))
      (node (ref "IC3") (pin "T14") (pinfunction "PC19_T14") (pintype "bidirectional"))
    )
    (net (code "185") (name "DATA20") (class "Default")
      (node (ref "IC2") (pin "C8") (pinfunction "DQ4_C8") (pintype "tri_state"))
      (node (ref "IC3") (pin "U16") (pinfunction "PC20_U16") (pintype "bidirectional"))
    )
    (net (code "186") (name "DATA21") (class "Default")
      (node (ref "IC2") (pin "D9") (pinfunction "DQ5_D9") (pintype "tri_state"))
      (node (ref "IC3") (pin "T15") (pinfunction "PC21_T15") (pintype "bidirectional"))
    )
    (net (code "187") (name "DATA22") (class "Default")
      (node (ref "IC2") (pin "D8") (pinfunction "DQ6_D8") (pintype "tri_state"))
      (node (ref "IC3") (pin "U17") (pinfunction "PC22_U17") (pintype "bidirectional"))
    )
    (net (code "188") (name "DATA23") (class "Default")
      (node (ref "IC2") (pin "E9") (pinfunction "DQ7_E9") (pintype "tri_state"))
      (node (ref "IC3") (pin "T16") (pinfunction "PC23_T16") (pintype "bidirectional"))
    )
    (net (code "189") (name "DATA24") (class "Default")
      (node (ref "IC2") (pin "E1") (pinfunction "DQ8_E1") (pintype "tri_state"))
      (node (ref "IC3") (pin "R15") (pinfunction "PC24_R15") (pintype "bidirectional"))
    )
    (net (code "190") (name "DATA25") (class "Default")
      (node (ref "IC2") (pin "D2") (pinfunction "DQ9_D2") (pintype "tri_state"))
      (node (ref "IC3") (pin "T17") (pinfunction "PC25_T17") (pintype "bidirectional"))
    )
    (net (code "191") (name "DATA26") (class "Default")
      (node (ref "IC2") (pin "D1") (pinfunction "DQ10_D1") (pintype "tri_state"))
      (node (ref "IC3") (pin "P14") (pinfunction "PC26_P14") (pintype "bidirectional"))
    )
    (net (code "192") (name "DATA27") (class "Default")
      (node (ref "IC2") (pin "C2") (pinfunction "DQ11_C2") (pintype "tri_state"))
      (node (ref "IC3") (pin "P15") (pinfunction "PC27_P15") (pintype "bidirectional"))
    )
    (net (code "193") (name "DATA28") (class "Default")
      (node (ref "IC2") (pin "C1") (pinfunction "DQ12_C1") (pintype "tri_state"))
      (node (ref "IC3") (pin "N13") (pinfunction "PC28_N13") (pintype "bidirectional"))
    )
    (net (code "194") (name "DATA29") (class "Default")
      (node (ref "IC2") (pin "B2") (pinfunction "DQ13_B2") (pintype "tri_state"))
      (node (ref "IC3") (pin "R16") (pinfunction "PC29_R16") (pintype "bidirectional"))
    )
    (net (code "195") (name "DATA30") (class "Default")
      (node (ref "IC2") (pin "B1") (pinfunction "DQ14_B1") (pintype "tri_state"))
      (node (ref "IC3") (pin "N15") (pinfunction "PC30_N15") (pintype "bidirectional"))
    )
    (net (code "196") (name "DATA31") (class "Default")
      (node (ref "IC2") (pin "A2") (pinfunction "DQ15_A2") (pintype "tri_state"))
      (node (ref "IC3") (pin "N14") (pinfunction "PC31_N14") (pintype "bidirectional"))
    )
    (net (code "197") (name "DDM") (class "Default")
      (node (ref "IC3") (pin "K2") (pinfunction "DM_K2") (pintype "power_in"))
    )
    (net (code "198") (name "DDP") (class "Default")
      (node (ref "IC3") (pin "K5") (pinfunction "DP_K5") (pintype "power_in"))
    )
    (net (code "199") (name "GND") (class "Default")
      (node (ref "C1") (pin "2") (pinfunction "2_2") (pintype "passive"))
      (node (ref "C10") (pin "2") (pinfunction "2_2") (pintype "passive"))
      (node (ref "C11") (pin "2") (pinfunction "2_2") (pintype "passive"))
      (node (ref "C12") (pin "2") (pinfunction "2_2") (pintype "passive"))
      (node (ref "C13") (pin "2") (pinfunction "2_2") (pintype "passive"))
      (node (ref "C14") (pin "2") (pinfunction "2_2") (pintype "passive"))
      (node (ref "C15") (pin "2") (pinfunction "2_2") (pintype "passive"))
      (node (ref "C16") (pin "2") (pinfunction "2_2") (pintype "passive"))
      (node (ref "C17") (pin "2") (pinfunction "2_2") (pintype "passive"))
      (node (ref "C18") (pin "2") (pinfunction "2_2") (pintype "passive"))
      (node (ref "C19") (pin "2") (pinfunction "2_2") (pintype "passive"))
      (node (ref "C2") (pin "2") (pinfunction "2_2") (pintype "passive"))
      (node (ref "C20") (pin "2") (pinfunction "2_2") (pintype "passive"))
      (node (ref "C21") (pin "2") (pinfunction "2_2") (pintype "passive"))
      (node (ref "C22") (pin "2") (pinfunction "2_2") (pintype "passive"))
      (node (ref "C23") (pin "2") (pinfunction "2_2") (pintype "passive"))
      (node (ref "C24") (pin "2") (pinfunction "2_2") (pintype "passive"))
      (node (ref "C25") (pin "2") (pinfunction "2_2") (pintype "passive"))
      (node (ref "C26") (pin "2") (pinfunction "2_2") (pintype "passive"))
      (node (ref "C27") (pin "2") (pinfunction "2_2") (pintype "passive"))
      (node (ref "C28") (pin "2") (pinfunction "2_2") (pintype "passive"))
      (node (ref "C29") (pin "2") (pinfunction "2_2") (pintype "passive"))
      (node (ref "C3") (pin "2") (pinfunction "2_2") (pintype "passive"))
      (node (ref "C30") (pin "2") (pinfunction "2_2") (pintype "passive"))
      (node (ref "C31") (pin "2") (pinfunction "2_2") (pintype "passive"))
      (node (ref "C32") (pin "2") (pinfunction "2_2") (pintype "passive"))
      (node (ref "C33") (pin "2") (pinfunction "2_2") (pintype "passive"))
      (node (ref "C34") (pin "2") (pinfunction "2_2") (pintype "passive"))
      (node (ref "C35") (pin "2") (pinfunction "2_2") (pintype "passive"))
      (node (ref "C36") (pin "2") (pinfunction "2_2") (pintype "passive"))
      (node (ref "C37") (pin "2") (pinfunction "2_2") (pintype "passive"))
      (node (ref "C38") (pin "2") (pinfunction "2_2") (pintype "passive"))
      (node (ref "C39") (pin "2") (pinfunction "2_2") (pintype "passive"))
      (node (ref "C4") (pin "2") (pinfunction "2_2") (pintype "passive"))
      (node (ref "C40") (pin "2") (pinfunction "2_2") (pintype "passive"))
      (node (ref "C41") (pin "2") (pinfunction "2_2") (pintype "passive"))
      (node (ref "C42") (pin "2") (pinfunction "2_2") (pintype "passive"))
      (node (ref "C5") (pin "2") (pinfunction "2_2") (pintype "passive"))
      (node (ref "C6") (pin "2") (pinfunction "2_2") (pintype "passive"))
      (node (ref "C7") (pin "2") (pinfunction "2_2") (pintype "passive"))
      (node (ref "C8") (pin "2") (pinfunction "2_2") (pintype "passive"))
      (node (ref "C9") (pin "2") (pinfunction "2_2") (pintype "passive"))
      (node (ref "CON1") (pin "5") (pinfunction "GND_5") (pintype "bidirectional"))
      (node (ref "CON1") (pin "SH1") (pinfunction "GND_SH1") (pintype "bidirectional"))
      (node (ref "CON1") (pin "SH2") (pinfunction "GND_SH2") (pintype "bidirectional"))
      (node (ref "CON1") (pin "SH3") (pinfunction "GND_SH3") (pintype "bidirectional"))
      (node (ref "CON1") (pin "SH4") (pinfunction "GND_SH4") (pintype "bidirectional"))
      (node (ref "CON1") (pin "SH5") (pinfunction "GND_SH5") (pintype "bidirectional"))
      (node (ref "CON1") (pin "SH6") (pinfunction "GND_SH6") (pintype "bidirectional"))
      (node (ref "CON1") (pin "SH7") (pinfunction "GND_SH7") (pintype "bidirectional"))
      (node (ref "CON1") (pin "SH8") (pinfunction "GND_SH8") (pintype "bidirectional"))
      (node (ref "CON2") (pin "GND1") (pinfunction "GND_GND1") (pintype "power_in"))
      (node (ref "CON2") (pin "GND2") (pinfunction "GND_GND2") (pintype "power_in"))
      (node (ref "CON2") (pin "GND3") (pinfunction "GND_GND3") (pintype "power_in"))
      (node (ref "CON2") (pin "GND4") (pinfunction "GND_GND4") (pintype "power_in"))
      (node (ref "CON2") (pin "P$6") (pinfunction "VSS_P$6") (pintype "bidirectional"))
      (node (ref "IC1") (pin "A1") (pinfunction "VSS_A1") (pintype "power_in"))
      (node (ref "IC1") (pin "A3") (pinfunction "VSSQ_A3") (pintype "power_in"))
      (node (ref "IC1") (pin "B7") (pinfunction "VSSQ_B7") (pintype "power_in"))
      (node (ref "IC1") (pin "C3") (pinfunction "VSSQ_C3") (pintype "power_in"))
      (node (ref "IC1") (pin "D7") (pinfunction "VSSQ_D7") (pintype "power_in"))
      (node (ref "IC1") (pin "E3") (pinfunction "VSS_E3") (pintype "power_in"))
      (node (ref "IC1") (pin "J1") (pinfunction "VSS_J1") (pintype "power_in"))
      (node (ref "IC2") (pin "A1") (pinfunction "VSS_A1") (pintype "power_in"))
      (node (ref "IC2") (pin "A3") (pinfunction "VSSQ_A3") (pintype "power_in"))
      (node (ref "IC2") (pin "B7") (pinfunction "VSSQ_B7") (pintype "power_in"))
      (node (ref "IC2") (pin "C3") (pinfunction "VSSQ_C3") (pintype "power_in"))
      (node (ref "IC2") (pin "D7") (pinfunction "VSSQ_D7") (pintype "power_in"))
      (node (ref "IC2") (pin "E3") (pinfunction "VSS_E3") (pintype "power_in"))
      (node (ref "IC2") (pin "J1") (pinfunction "VSS_J1") (pintype "power_in"))
      (node (ref "IC3") (pin "A14") (pinfunction "VSSI_A14") (pintype "power_in"))
      (node (ref "IC3") (pin "B7") (pinfunction "MIX33VSS_B7") (pintype "power_in"))
      (node (ref "IC3") (pin "C11") (pinfunction "MIX33VSS_C11") (pintype "power_in"))
      (node (ref "IC3") (pin "C15") (pinfunction "MIX33VSS_C15") (pintype "power_in"))
      (node (ref "IC3") (pin "D1") (pinfunction "TST1_D1") (pintype "input"))
      (node (ref "IC3") (pin "D11") (pinfunction "MIX33VSS_D11") (pintype "power_in"))
      (node (ref "IC3") (pin "D4") (pinfunction "MIX33VSS_D4") (pintype "power_in"))
      (node (ref "IC3") (pin "E3") (pinfunction "MIX33VSS_E3") (pintype "power_in"))
      (node (ref "IC3") (pin "E4") (pinfunction "TST0_E4") (pintype "input"))
      (node (ref "IC3") (pin "E6") (pinfunction "MIX33VSS_E6") (pintype "power_in"))
      (node (ref "IC3") (pin "E8") (pinfunction "MIX33VSS_E8") (pintype "power_in"))
      (node (ref "IC3") (pin "F2") (pinfunction "VSSI_F2") (pintype "power_in"))
      (node (ref "IC3") (pin "G3") (pinfunction "MIX33VSS_G3") (pintype "power_in"))
      (node (ref "IC3") (pin "H15") (pinfunction "VSSI_H15") (pintype "power_in"))
      (node (ref "IC3") (pin "H16") (pinfunction "MIX33VSS_H16") (pintype "power_in"))
      (node (ref "IC3") (pin "J12") (pinfunction "MIX33VSS_J12") (pintype "power_in"))
      (node (ref "IC3") (pin "J13") (pinfunction "VSSI_J13") (pintype "power_in"))
      (node (ref "IC3") (pin "J16") (pinfunction "VSSI_J16") (pintype "power_in"))
      (node (ref "IC3") (pin "L1") (pinfunction "MIX33VSS_L1") (pintype "power_in"))
      (node (ref "IC3") (pin "L5") (pinfunction "MIX33VSS_L5") (pintype "power_in"))
      (node (ref "IC3") (pin "M12") (pinfunction "MIX33VSS_M12") (pintype "power_in"))
      (node (ref "IC3") (pin "M16") (pinfunction "VSSI_M16") (pintype "power_in"))
      (node (ref "IC3") (pin "M2") (pinfunction "MIX33VSS_M2") (pintype "power_in"))
      (node (ref "IC3") (pin "M7") (pinfunction "MIX33VSS_M7") (pintype "power_in"))
      (node (ref "IC3") (pin "N12") (pinfunction "VSSI_N12") (pintype "power_in"))
      (node (ref "IC3") (pin "P17") (pinfunction "MIX33VSS_P17") (pintype "power_in"))
      (node (ref "IC3") (pin "R1") (pinfunction "MIX33VSS_R1") (pintype "power_in"))
      (node (ref "IC3") (pin "R2") (pinfunction "VSSI_R2") (pintype "power_in"))
      (node (ref "IC3") (pin "T13") (pinfunction "MIX33VSS_T13") (pintype "power_in"))
      (node (ref "IC3") (pin "T9") (pinfunction "MIX33VSS_T9") (pintype "power_in"))
      (node (ref "IC3") (pin "U2") (pinfunction "VSSI_U2") (pintype "power_in"))
      (node (ref "IC3") (pin "U5") (pinfunction "MIX33VSS_U5") (pintype "power_in"))
    )
    (net (code "200") (name "HDMA") (class "Default")
      (node (ref "IC3") (pin "K3") (pinfunction "HDMA_K3") (pintype "power_in"))
    )
    (net (code "201") (name "HDMB") (class "Default")
      (node (ref "IC3") (pin "L3") (pinfunction "HDMB_L3") (pintype "power_in"))
    )
    (net (code "202") (name "HDPA") (class "Default")
      (node (ref "IC3") (pin "K1") (pinfunction "HDPA_K1") (pintype "power_in"))
    )
    (net (code "203") (name "HDPB") (class "Default")
      (node (ref "IC3") (pin "L2") (pinfunction "HDPB_L2") (pintype "power_in"))
    )
    (net (code "204") (name "HSE_IN") (class "Default")
      (node (ref "C25") (pin "1") (pinfunction "1_1") (pintype "passive"))
      (node (ref "IC3") (pin "J17") (pinfunction "OSC9M_XIN_J17") (pintype "power_in"))
      (node (ref "Q1") (pin "1") (pinfunction "1_1") (pintype "passive"))
    )
    (net (code "205") (name "HSE_OUT") (class "Default")
      (node (ref "C26") (pin "1") (pinfunction "1_1") (pintype "passive"))
      (node (ref "IC3") (pin "K17") (pinfunction "OSC9M_XOUT_K17") (pintype "power_in"))
      (node (ref "Q1") (pin "3") (pinfunction "2_3") (pintype "passive"))
    )
    (net (code "206") (name "LSE_IN") (class "Default")
      (node (ref "C27") (pin "1") (pinfunction "1_1") (pintype "passive"))
      (node (ref "IC3") (pin "H17") (pinfunction "OSC32K_XOUT_H17") (pintype "power_in"))
      (node (ref "Q2") (pin "1") (pinfunction "1_1") (pintype "passive"))
    )
    (net (code "207") (name "LSE_OUT") (class "Default")
      (node (ref "C28") (pin "1") (pinfunction "1_1") (pintype "passive"))
      (node (ref "IC3") (pin "G17") (pinfunction "OSC32K_XIN_G17") (pintype "power_in"))
      (node (ref "Q2") (pin "2") (pinfunction "2_2") (pintype "passive"))
    )
    (net (code "208") (name "NCS0") (class "Default")
      (node (ref "IC3") (pin "U6") (pinfunction "NCS0_BFCS_U6") (pintype "output"))
    )
    (net (code "209") (name "NCS2") (class "Default")
      (node (ref "IC3") (pin "T6") (pinfunction "NCS2_T6") (pintype "output"))
    )
    (net (code "210") (name "NCS3") (class "Default")
      (node (ref "IC3") (pin "R7") (pinfunction "NCS3_R7") (pintype "output"))
    )
    (net (code "211") (name "NWAIT") (class "Default")
      (node (ref "IC3") (pin "K15") (pinfunction "PC6_K15") (pintype "bidirectional"))
    )
    (net (code "212") (name "Net-(C21-Pad1)") (class "Default")
      (node (ref "C21") (pin "1") (pinfunction "1_1") (pintype "passive"))
      (node (ref "R1") (pin "1") (pinfunction "1_1") (pintype "passive"))
    )
    (net (code "213") (name "Net-(C23-Pad1)") (class "Default")
      (node (ref "C23") (pin "1") (pinfunction "1_1") (pintype "passive"))
      (node (ref "R2") (pin "1") (pinfunction "1_1") (pintype "passive"))
    )
    (net (code "214") (name "PLLRCA") (class "Default")
      (node (ref "C22") (pin "1") (pinfunction "1_1") (pintype "passive"))
      (node (ref "IC3") (pin "L17") (pinfunction "PLL_A_RC_L17") (pintype "power_in"))
      (node (ref "R1") (pin "2") (pinfunction "2_2") (pintype "passive"))
    )
    (net (code "215") (name "PLLRCB") (class "Default")
      (node (ref "C24") (pin "1") (pinfunction "1_1") (pintype "passive"))
      (node (ref "IC3") (pin "F17") (pinfunction "PLL_B_RC_F17") (pintype "power_in"))
      (node (ref "R2") (pin "2") (pinfunction "2_2") (pintype "passive"))
    )
    (net (code "216") (name "RAS") (class "Default")
      (node (ref "IC1") (pin "F8") (pinfunction "~{RAS}_F8") (pintype "input"))
      (node (ref "IC2") (pin "F8") (pinfunction "~{RAS}_F8") (pintype "input"))
      (node (ref "IC3") (pin "N10") (pinfunction "RAS_N10") (pintype "output"))
    )
    (net (code "217") (name "SDA10") (class "Default")
      (node (ref "IC1") (pin "H9") (pinfunction "A10_H9") (pintype "input"))
      (node (ref "IC2") (pin "H9") (pinfunction "A10_H9") (pintype "input"))
      (node (ref "IC3") (pin "N6") (pinfunction "A10_SDRAM_N6") (pintype "output"))
    )
    (net (code "218") (name "SDCK") (class "Default")
      (node (ref "IC1") (pin "F2") (pinfunction "CLK_F2") (pintype "input"))
      (node (ref "IC2") (pin "F2") (pinfunction "CLK_F2") (pintype "input"))
      (node (ref "IC3") (pin "U7") (pinfunction "SDRAMCLK_U7") (pintype "power_in"))
    )
    (net (code "219") (name "SDCKE") (class "Default")
      (node (ref "IC1") (pin "F3") (pinfunction "CKE_F3") (pintype "input"))
      (node (ref "IC2") (pin "F3") (pinfunction "CKE_F3") (pintype "input"))
      (node (ref "IC3") (pin "P9") (pinfunction "SDRAMCKE_P9") (pintype "output"))
    )
    (net (code "220") (name "SDCS") (class "Default")
      (node (ref "IC1") (pin "G9") (pinfunction "\\CS_G9") (pintype "input"))
      (node (ref "IC2") (pin "G9") (pinfunction "\\CS_G9") (pintype "input"))
      (node (ref "IC3") (pin "M9") (pinfunction "NCS1_SDCS_M9") (pintype "output"))
    )
    (net (code "221") (name "SDWE") (class "Default")
      (node (ref "IC1") (pin "F9") (pinfunction "~{WE}_F9") (pintype "input"))
      (node (ref "IC2") (pin "F9") (pinfunction "~{WE}_F9") (pintype "input"))
      (node (ref "IC3") (pin "T8") (pinfunction "WE_T8") (pintype "output"))
    )
    (net (code "222") (name "VDDCORE") (class "Default")
      (node (ref "C13") (pin "1") (pinfunction "1_1") (pintype "passive"))
      (node (ref "C14") (pin "1") (pinfunction "1_1") (pintype "passive"))
      (node (ref "C15") (pin "1") (pinfunction "1_1") (pintype "passive"))
      (node (ref "C16") (pin "1") (pinfunction "1_1") (pintype "passive"))
      (node (ref "C17") (pin "1") (pinfunction "1_1") (pintype "passive"))
      (node (ref "C18") (pin "1") (pinfunction "1_1") (pintype "passive"))
      (node (ref "C19") (pin "1") (pinfunction "1_1") (pintype "passive"))
      (node (ref "C20") (pin "1") (pinfunction "1_1") (pintype "passive"))
      (node (ref "IC3") (pin "C14") (pinfunction "VDDI_C14") (pintype "power_in"))
      (node (ref "IC3") (pin "F6") (pinfunction "VDDI_F6") (pintype "power_in"))
      (node (ref "IC3") (pin "H13") (pinfunction "VDDI_H13") (pintype "power_in"))
      (node (ref "IC3") (pin "J14") (pinfunction "VDDI_J14") (pintype "power_in"))
      (node (ref "IC3") (pin "J15") (pinfunction "VDDI_J15") (pintype "power_in"))
      (node (ref "IC3") (pin "L16") (pinfunction "VDDI_L16") (pintype "power_in"))
      (node (ref "IC3") (pin "T10") (pinfunction "VDDI_T10") (pintype "power_in"))
      (node (ref "IC3") (pin "T2") (pinfunction "VDDI_T2") (pintype "power_in"))
      (node (ref "IC3") (pin "U1") (pinfunction "VDDI_U1") (pintype "power_in"))
    )
    (net (code "223") (name "unconnected-(C43-Pad1)") (class "Default")
      (node (ref "C43") (pin "1") (pinfunction "1_1") (pintype "passive"))
    )
    (net (code "224") (name "unconnected-(C43-Pad2)") (class "Default")
      (node (ref "C43") (pin "2") (pinfunction "2_2") (pintype "passive"))
    )
    (net (code "225") (name "unconnected-(CON1-DM-Pad2)") (class "Default")
      (node (ref "CON1") (pin "2") (pinfunction "DM_2") (pintype "bidirectional"))
    )
    (net (code "226") (name "unconnected-(CON1-DP-Pad3)") (class "Default")
      (node (ref "CON1") (pin "3") (pinfunction "DP_3") (pintype "bidirectional"))
    )
    (net (code "227") (name "unconnected-(CON1-ID-Pad4)") (class "Default")
      (node (ref "CON1") (pin "4") (pinfunction "ID_4") (pintype "bidirectional"))
    )
    (net (code "228") (name "unconnected-(CON1-VCC-Pad1)") (class "Default")
      (node (ref "CON1") (pin "1") (pinfunction "VCC_1") (pintype "bidirectional"))
    )
    (net (code "229") (name "unconnected-(CON2-CD{slash}DAT3-PadP$2)") (class "Default")
      (node (ref "CON2") (pin "P$2") (pinfunction "CD/DAT3_P$2") (pintype "input"))
    )
    (net (code "230") (name "unconnected-(CON2-CLK-PadP$5)") (class "Default")
      (node (ref "CON2") (pin "P$5") (pinfunction "CLK_P$5") (pintype "bidirectional"))
    )
    (net (code "231") (name "unconnected-(CON2-CMD-PadP$3)") (class "Default")
      (node (ref "CON2") (pin "P$3") (pinfunction "CMD_P$3") (pintype "input"))
    )
    (net (code "232") (name "unconnected-(CON2-DAT0-PadP$7)") (class "Default")
      (node (ref "CON2") (pin "P$7") (pinfunction "DAT0_P$7") (pintype "power_in"))
    )
    (net (code "233") (name "unconnected-(CON2-DAT1-PadP$8)") (class "Default")
      (node (ref "CON2") (pin "P$8") (pinfunction "DAT1_P$8") (pintype "power_in"))
    )
    (net (code "234") (name "unconnected-(CON2-DAT2-PadP$1)") (class "Default")
      (node (ref "CON2") (pin "P$1") (pinfunction "DAT2_P$1") (pintype "output"))
    )
    (net (code "235") (name "unconnected-(CON2-VDD-PadP$4)") (class "Default")
      (node (ref "CON2") (pin "P$4") (pinfunction "VDD_P$4") (pintype "input"))
    )
    (net (code "236") (name "unconnected-(IC1A-NC-PadE2)") (class "Default")
      (node (ref "IC1") (pin "E2") (pinfunction "NC_E2") (pintype "no_connect"))
    )
    (net (code "237") (name "unconnected-(IC2A-NC-PadE2)") (class "Default")
      (node (ref "IC2") (pin "E2") (pinfunction "NC_E2") (pintype "no_connect"))
    )
    (net (code "238") (name "unconnected-(IC3-ICETCK-PadE5)") (class "Default")
      (node (ref "IC3") (pin "E5") (pinfunction "ICETCK_E5") (pintype "input"))
    )
    (net (code "239") (name "unconnected-(IC3-ICETDI-PadA1)") (class "Default")
      (node (ref "IC3") (pin "A1") (pinfunction "ICETDI_A1") (pintype "input"))
    )
    (net (code "240") (name "unconnected-(IC3-ICETDO-PadB1)") (class "Default")
      (node (ref "IC3") (pin "B1") (pinfunction "ICETDO_B1") (pintype "output"))
    )
    (net (code "241") (name "unconnected-(IC3-ICETMS-PadC1)") (class "Default")
      (node (ref "IC3") (pin "C1") (pinfunction "ICETMS_C1") (pintype "input"))
    )
    (net (code "242") (name "unconnected-(IC3-JTAGSEL-PadA2)") (class "Default")
      (node (ref "IC3") (pin "A2") (pinfunction "JTAGSEL_A2") (pintype "input"))
    )
    (net (code "243") (name "unconnected-(IC3-NRST-PadE1)") (class "Default")
      (node (ref "IC3") (pin "E1") (pinfunction "NRST_E1") (pintype "power_in"))
    )
    (net (code "244") (name "unconnected-(IC3-NRW0NWE-PadP8)") (class "Default")
      (node (ref "IC3") (pin "P8") (pinfunction "NRW0NWE_P8") (pintype "bidirectional"))
    )
    (net (code "245") (name "unconnected-(IC3-NTRST-PadE2)") (class "Default")
      (node (ref "IC3") (pin "E2") (pinfunction "NTRST_E2") (pintype "input"))
    )
    (net (code "246") (name "unconnected-(IC3-PA0-PadG13)") (class "Default")
      (node (ref "IC3") (pin "G13") (pinfunction "PA0_G13") (pintype "bidirectional"))
    )
    (net (code "247") (name "unconnected-(IC3-PA1-PadG14)") (class "Default")
      (node (ref "IC3") (pin "G14") (pinfunction "PA1_G14") (pintype "bidirectional"))
    )
    (net (code "248") (name "unconnected-(IC3-PA2-PadG15)") (class "Default")
      (node (ref "IC3") (pin "G15") (pinfunction "PA2_G15") (pintype "bidirectional"))
    )
    (net (code "249") (name "unconnected-(IC3-PA3-PadG16)") (class "Default")
      (node (ref "IC3") (pin "G16") (pinfunction "PA3_G16") (pintype "bidirectional"))
    )
    (net (code "250") (name "unconnected-(IC3-PA4-PadF13)") (class "Default")
      (node (ref "IC3") (pin "F13") (pinfunction "PA4_F13") (pintype "bidirectional"))
    )
    (net (code "251") (name "unconnected-(IC3-PA5-PadF16)") (class "Default")
      (node (ref "IC3") (pin "F16") (pinfunction "PA5_F16") (pintype "bidirectional"))
    )
    (net (code "252") (name "unconnected-(IC3-PA6-PadE15)") (class "Default")
      (node (ref "IC3") (pin "E15") (pinfunction "PA6_E15") (pintype "bidirectional"))
    )
    (net (code "253") (name "unconnected-(IC3-PA7-PadB17)") (class "Default")
      (node (ref "IC3") (pin "B17") (pinfunction "PA7_B17") (pintype "bidirectional"))
    )
    (net (code "254") (name "unconnected-(IC3-PA8-PadC16)") (class "Default")
      (node (ref "IC3") (pin "C16") (pinfunction "PA8_C16") (pintype "bidirectional"))
    )
    (net (code "255") (name "unconnected-(IC3-PA9-PadE14)") (class "Default")
      (node (ref "IC3") (pin "E14") (pinfunction "PA9_E14") (pintype "bidirectional"))
    )
    (net (code "256") (name "unconnected-(IC3-PA10-PadD15)") (class "Default")
      (node (ref "IC3") (pin "D15") (pinfunction "PA10_D15") (pintype "bidirectional"))
    )
    (net (code "257") (name "unconnected-(IC3-PA11-PadB15)") (class "Default")
      (node (ref "IC3") (pin "B15") (pinfunction "PA11_B15") (pintype "bidirectional"))
    )
    (net (code "258") (name "unconnected-(IC3-PA12-PadB16)") (class "Default")
      (node (ref "IC3") (pin "B16") (pinfunction "PA12_B16") (pintype "bidirectional"))
    )
    (net (code "259") (name "unconnected-(IC3-PA13-PadA17)") (class "Default")
      (node (ref "IC3") (pin "A17") (pinfunction "PA13_A17") (pintype "bidirectional"))
    )
    (net (code "260") (name "unconnected-(IC3-PA14-PadA15)") (class "Default")
      (node (ref "IC3") (pin "A15") (pinfunction "PA14_A15") (pintype "bidirectional"))
    )
    (net (code "261") (name "unconnected-(IC3-PA15-PadB14)") (class "Default")
      (node (ref "IC3") (pin "B14") (pinfunction "PA15_B14") (pintype "bidirectional"))
    )
    (net (code "262") (name "unconnected-(IC3-PA16-PadD14)") (class "Default")
      (node (ref "IC3") (pin "D14") (pinfunction "PA16_D14") (pintype "bidirectional"))
    )
    (net (code "263") (name "unconnected-(IC3-PA17-PadB13)") (class "Default")
      (node (ref "IC3") (pin "B13") (pinfunction "PA17_B13") (pintype "bidirectional"))
    )
    (net (code "264") (name "unconnected-(IC3-PA18-PadC13)") (class "Default")
      (node (ref "IC3") (pin "C13") (pinfunction "PA18_C13") (pintype "bidirectional"))
    )
    (net (code "265") (name "unconnected-(IC3-PA19-PadA13)") (class "Default")
      (node (ref "IC3") (pin "A13") (pinfunction "PA19_A13") (pintype "bidirectional"))
    )
    (net (code "266") (name "unconnected-(IC3-PA20-PadC12)") (class "Default")
      (node (ref "IC3") (pin "C12") (pinfunction "PA20_C12") (pintype "bidirectional"))
    )
    (net (code "267") (name "unconnected-(IC3-PA21-PadD13)") (class "Default")
      (node (ref "IC3") (pin "D13") (pinfunction "PA21_D13") (pintype "bidirectional"))
    )
    (net (code "268") (name "unconnected-(IC3-PA22-PadD12)") (class "Default")
      (node (ref "IC3") (pin "D12") (pinfunction "PA22_D12") (pintype "bidirectional"))
    )
    (net (code "269") (name "unconnected-(IC3-PA23-PadA12)") (class "Default")
      (node (ref "IC3") (pin "A12") (pinfunction "PA23_A12") (pintype "bidirectional"))
    )
    (net (code "270") (name "unconnected-(IC3-PA24-PadB12)") (class "Default")
      (node (ref "IC3") (pin "B12") (pinfunction "PA24_B12") (pintype "bidirectional"))
    )
    (net (code "271") (name "unconnected-(IC3-PA25-PadE13)") (class "Default")
      (node (ref "IC3") (pin "E13") (pinfunction "PA25_E13") (pintype "bidirectional"))
    )
    (net (code "272") (name "unconnected-(IC3-PA26-PadE12)") (class "Default")
      (node (ref "IC3") (pin "E12") (pinfunction "PA26_E12") (pintype "bidirectional"))
    )
    (net (code "273") (name "unconnected-(IC3-PA27-PadG12)") (class "Default")
      (node (ref "IC3") (pin "G12") (pinfunction "PA27_G12") (pintype "bidirectional"))
    )
    (net (code "274") (name "unconnected-(IC3-PA28-PadF12)") (class "Default")
      (node (ref "IC3") (pin "F12") (pinfunction "PA28_F12") (pintype "bidirectional"))
    )
    (net (code "275") (name "unconnected-(IC3-PA29-PadE11)") (class "Default")
      (node (ref "IC3") (pin "E11") (pinfunction "PA29_E11") (pintype "bidirectional"))
    )
    (net (code "276") (name "unconnected-(IC3-PA30-PadF11)") (class "Default")
      (node (ref "IC3") (pin "F11") (pinfunction "PA30_F11") (pintype "bidirectional"))
    )
    (net (code "277") (name "unconnected-(IC3-PA31-PadA10)") (class "Default")
      (node (ref "IC3") (pin "A10") (pinfunction "PA31_A10") (pintype "bidirectional"))
    )
    (net (code "278") (name "unconnected-(IC3-PB0-PadB10)") (class "Default")
      (node (ref "IC3") (pin "B10") (pinfunction "PB0_B10") (pintype "bidirectional"))
    )
    (net (code "279") (name "unconnected-(IC3-PB1-PadC10)") (class "Default")
      (node (ref "IC3") (pin "C10") (pinfunction "PB1_C10") (pintype "bidirectional"))
    )
    (net (code "280") (name "unconnected-(IC3-PB2-PadD10)") (class "Default")
      (node (ref "IC3") (pin "D10") (pinfunction "PB2_D10") (pintype "bidirectional"))
    )
    (net (code "281") (name "unconnected-(IC3-PB3-PadE10)") (class "Default")
      (node (ref "IC3") (pin "E10") (pinfunction "PB3_E10") (pintype "bidirectional"))
    )
    (net (code "282") (name "unconnected-(IC3-PB4-PadA9)") (class "Default")
      (node (ref "IC3") (pin "A9") (pinfunction "PB4_A9") (pintype "bidirectional"))
    )
    (net (code "283") (name "unconnected-(IC3-PB5-PadB9)") (class "Default")
      (node (ref "IC3") (pin "B9") (pinfunction "PB5_B9") (pintype "bidirectional"))
    )
    (net (code "284") (name "unconnected-(IC3-PB6-PadC9)") (class "Default")
      (node (ref "IC3") (pin "C9") (pinfunction "PB6_C9") (pintype "bidirectional"))
    )
    (net (code "285") (name "unconnected-(IC3-PB7-PadE9)") (class "Default")
      (node (ref "IC3") (pin "E9") (pinfunction "PB7_E9") (pintype "bidirectional"))
    )
    (net (code "286") (name "unconnected-(IC3-PB8-PadD9)") (class "Default")
      (node (ref "IC3") (pin "D9") (pinfunction "PB8_D9") (pintype "bidirectional"))
    )
    (net (code "287") (name "unconnected-(IC3-PB9-PadA8)") (class "Default")
      (node (ref "IC3") (pin "A8") (pinfunction "PB9_A8") (pintype "bidirectional"))
    )
    (net (code "288") (name "unconnected-(IC3-PB10-PadB8)") (class "Default")
      (node (ref "IC3") (pin "B8") (pinfunction "PB10_B8") (pintype "bidirectional"))
    )
    (net (code "289") (name "unconnected-(IC3-PB11-PadF9)") (class "Default")
      (node (ref "IC3") (pin "F9") (pinfunction "PB11_F9") (pintype "bidirectional"))
    )
    (net (code "290") (name "unconnected-(IC3-PB12-PadC8)") (class "Default")
      (node (ref "IC3") (pin "C8") (pinfunction "PB12_C8") (pintype "bidirectional"))
    )
    (net (code "291") (name "unconnected-(IC3-PB13-PadC7)") (class "Default")
      (node (ref "IC3") (pin "C7") (pinfunction "PB13_C7") (pintype "bidirectional"))
    )
    (net (code "292") (name "unconnected-(IC3-PB14-PadD7)") (class "Default")
      (node (ref "IC3") (pin "D7") (pinfunction "PB14_D7") (pintype "bidirectional"))
    )
    (net (code "293") (name "unconnected-(IC3-PB15-PadE7)") (class "Default")
      (node (ref "IC3") (pin "E7") (pinfunction "PB15_E7") (pintype "bidirectional"))
    )
    (net (code "294") (name "unconnected-(IC3-PB16-PadF7)") (class "Default")
      (node (ref "IC3") (pin "F7") (pinfunction "PB16_F7") (pintype "bidirectional"))
    )
    (net (code "295") (name "unconnected-(IC3-PB17-PadA4)") (class "Default")
      (node (ref "IC3") (pin "A4") (pinfunction "PB17_A4") (pintype "bidirectional"))
    )
    (net (code "296") (name "unconnected-(IC3-PB18-PadB3)") (class "Default")
      (node (ref "IC3") (pin "B3") (pinfunction "PB18_B3") (pintype "bidirectional"))
    )
    (net (code "297") (name "unconnected-(IC3-PB19-PadC5)") (class "Default")
      (node (ref "IC3") (pin "C5") (pinfunction "PB19_C5") (pintype "bidirectional"))
    )
    (net (code "298") (name "unconnected-(IC3-PB20-PadA3)") (class "Default")
      (node (ref "IC3") (pin "A3") (pinfunction "PB20_A3") (pintype "bidirectional"))
    )
    (net (code "299") (name "unconnected-(IC3-PB21-PadB4)") (class "Default")
      (node (ref "IC3") (pin "B4") (pinfunction "PB21_B4") (pintype "bidirectional"))
    )
    (net (code "300") (name "unconnected-(IC3-PB22-PadC4)") (class "Default")
      (node (ref "IC3") (pin "C4") (pinfunction "PB22_C4") (pintype "bidirectional"))
    )
    (net (code "301") (name "unconnected-(IC3-PB23-PadF3)") (class "Default")
      (node (ref "IC3") (pin "F3") (pinfunction "PB23_F3") (pintype "bidirectional"))
    )
    (net (code "302") (name "unconnected-(IC3-PB24-PadF5)") (class "Default")
      (node (ref "IC3") (pin "F5") (pinfunction "PB24_F5") (pintype "bidirectional"))
    )
    (net (code "303") (name "unconnected-(IC3-PB25-PadF4)") (class "Default")
      (node (ref "IC3") (pin "F4") (pinfunction "PB25_F4") (pintype "bidirectional"))
    )
    (net (code "304") (name "unconnected-(IC3-PB26-PadG4)") (class "Default")
      (node (ref "IC3") (pin "G4") (pinfunction "PB26_G4") (pintype "bidirectional"))
    )
    (net (code "305") (name "unconnected-(IC3-PB27-PadG6)") (class "Default")
      (node (ref "IC3") (pin "G6") (pinfunction "PB27_G6") (pintype "bidirectional"))
    )
    (net (code "306") (name "unconnected-(IC3-PB28-PadJ5)") (class "Default")
      (node (ref "IC3") (pin "J5") (pinfunction "PB28_J5") (pintype "bidirectional"))
    )
    (net (code "307") (name "unconnected-(IC3-PB29-PadJ6)") (class "Default")
      (node (ref "IC3") (pin "J6") (pinfunction "PB29_J6") (pintype "bidirectional"))
    )
    (net (code "308") (name "unconnected-(IC3-PC0-PadM15)") (class "Default")
      (node (ref "IC3") (pin "M15") (pinfunction "PC0_M15") (pintype "bidirectional"))
    )
    (net (code "309") (name "unconnected-(IC3-PC1-PadM14)") (class "Default")
      (node (ref "IC3") (pin "M14") (pinfunction "PC1_M14") (pintype "bidirectional"))
    )
    (net (code "310") (name "unconnected-(IC3-PC2-PadL14)") (class "Default")
      (node (ref "IC3") (pin "L14") (pinfunction "PC2_L14") (pintype "bidirectional"))
    )
    (net (code "311") (name "unconnected-(IC3-PC3-PadL15)") (class "Default")
      (node (ref "IC3") (pin "L15") (pinfunction "PC3_L15") (pintype "bidirectional"))
    )
    (net (code "312") (name "unconnected-(IC3-PC4-PadK14)") (class "Default")
      (node (ref "IC3") (pin "K14") (pinfunction "PC4_K14") (pintype "bidirectional"))
    )
    (net (code "313") (name "unconnected-(IC3-PC5-PadK13)") (class "Default")
      (node (ref "IC3") (pin "K13") (pinfunction "PC5_K13") (pintype "bidirectional"))
    )
    (net (code "314") (name "unconnected-(IC3-PC8-PadR5)") (class "Default")
      (node (ref "IC3") (pin "R5") (pinfunction "PC8_R5") (pintype "bidirectional"))
    )
    (net (code "315") (name "unconnected-(IC3-PC9-PadP7)") (class "Default")
      (node (ref "IC3") (pin "P7") (pinfunction "PC9_P7") (pintype "bidirectional"))
    )
    (net (code "316") (name "unconnected-(IC3-PC10-PadL12)") (class "Default")
      (node (ref "IC3") (pin "L12") (pinfunction "PC10_L12") (pintype "bidirectional"))
    )
    (net (code "317") (name "unconnected-(IC3-PC11-PadN16)") (class "Default")
      (node (ref "IC3") (pin "N16") (pinfunction "PC11_N16") (pintype "bidirectional"))
    )
    (net (code "318") (name "unconnected-(IC3-PC12-PadN17)") (class "Default")
      (node (ref "IC3") (pin "N17") (pinfunction "PC12_N17") (pintype "bidirectional"))
    )
    (net (code "319") (name "unconnected-(IC3-PC13-PadM13)") (class "Default")
      (node (ref "IC3") (pin "M13") (pinfunction "PC13_M13") (pintype "bidirectional"))
    )
    (net (code "320") (name "unconnected-(IC3-PC14-PadM17)") (class "Default")
      (node (ref "IC3") (pin "M17") (pinfunction "PC14_M17") (pintype "bidirectional"))
    )
    (net (code "321") (name "unconnected-(IC3-PC15-PadL13)") (class "Default")
      (node (ref "IC3") (pin "L13") (pinfunction "PC15_L13") (pintype "bidirectional"))
    )
    (net (code "322") (name "unconnected-(IC3-PD0-PadE17)") (class "Default")
      (node (ref "IC3") (pin "E17") (pinfunction "PD0_E17") (pintype "bidirectional"))
    )
    (net (code "323") (name "unconnected-(IC3-PD1-PadF15)") (class "Default")
      (node (ref "IC3") (pin "F15") (pinfunction "PD1_F15") (pintype "bidirectional"))
    )
    (net (code "324") (name "unconnected-(IC3-PD2-PadF14)") (class "Default")
      (node (ref "IC3") (pin "F14") (pinfunction "PD2_F14") (pintype "bidirectional"))
    )
    (net (code "325") (name "unconnected-(IC3-PD3-PadE16)") (class "Default")
      (node (ref "IC3") (pin "E16") (pinfunction "PD3_E16") (pintype "bidirectional"))
    )
    (net (code "326") (name "unconnected-(IC3-PD4-PadD17)") (class "Default")
      (node (ref "IC3") (pin "D17") (pinfunction "PD4_D17") (pintype "bidirectional"))
    )
    (net (code "327") (name "unconnected-(IC3-PD5-PadC17)") (class "Default")
      (node (ref "IC3") (pin "C17") (pinfunction "PD5_C17") (pintype "bidirectional"))
    )
    (net (code "328") (name "unconnected-(IC3-PD6-PadD16)") (class "Default")
      (node (ref "IC3") (pin "D16") (pinfunction "PD6_D16") (pintype "bidirectional"))
    )
    (net (code "329") (name "unconnected-(IC3-PD7-PadD6)") (class "Default")
      (node (ref "IC3") (pin "D6") (pinfunction "PD7_D6") (pintype "bidirectional"))
    )
    (net (code "330") (name "unconnected-(IC3-PD8-PadA6)") (class "Default")
      (node (ref "IC3") (pin "A6") (pinfunction "PD8_A6") (pintype "bidirectional"))
    )
    (net (code "331") (name "unconnected-(IC3-PD9-PadB6)") (class "Default")
      (node (ref "IC3") (pin "B6") (pinfunction "PD9_B6") (pintype "bidirectional"))
    )
    (net (code "332") (name "unconnected-(IC3-PD10-PadC6)") (class "Default")
      (node (ref "IC3") (pin "C6") (pinfunction "PD10_C6") (pintype "bidirectional"))
    )
    (net (code "333") (name "unconnected-(IC3-PD11-PadA5)") (class "Default")
      (node (ref "IC3") (pin "A5") (pinfunction "PD11_A5") (pintype "bidirectional"))
    )
    (net (code "334") (name "unconnected-(IC3-PD12-PadB5)") (class "Default")
      (node (ref "IC3") (pin "B5") (pinfunction "PD12_B5") (pintype "bidirectional"))
    )
    (net (code "335") (name "unconnected-(IC3-PD13-PadB2)") (class "Default")
      (node (ref "IC3") (pin "B2") (pinfunction "PD13_B2") (pintype "bidirectional"))
    )
    (net (code "336") (name "unconnected-(IC3-PD14-PadC3)") (class "Default")
      (node (ref "IC3") (pin "C3") (pinfunction "PD14_C3") (pintype "bidirectional"))
    )
    (net (code "337") (name "unconnected-(IC3-PD15-PadC2)") (class "Default")
      (node (ref "IC3") (pin "C2") (pinfunction "PD15_C2") (pintype "bidirectional"))
    )
    (net (code "338") (name "unconnected-(IC3-PD16-PadF1)") (class "Default")
      (node (ref "IC3") (pin "F1") (pinfunction "PD16_F1") (pintype "bidirectional"))
    )
    (net (code "339") (name "unconnected-(IC3-PD17-PadG2)") (class "Default")
      (node (ref "IC3") (pin "G2") (pinfunction "PD17_G2") (pintype "bidirectional"))
    )
    (net (code "340") (name "unconnected-(IC3-PD18-PadG5)") (class "Default")
      (node (ref "IC3") (pin "G5") (pinfunction "PD18_G5") (pintype "bidirectional"))
    )
    (net (code "341") (name "unconnected-(IC3-PD19-PadG1)") (class "Default")
      (node (ref "IC3") (pin "G1") (pinfunction "PD19_G1") (pintype "bidirectional"))
    )
    (net (code "342") (name "unconnected-(IC3-PD20-PadH2)") (class "Default")
      (node (ref "IC3") (pin "H2") (pinfunction "PD20_H2") (pintype "bidirectional"))
    )
    (net (code "343") (name "unconnected-(IC3-PD21-PadH4)") (class "Default")
      (node (ref "IC3") (pin "H4") (pinfunction "PD21_H4") (pintype "bidirectional"))
    )
    (net (code "344") (name "unconnected-(IC3-PD22-PadH3)") (class "Default")
      (node (ref "IC3") (pin "H3") (pinfunction "PD22_H3") (pintype "bidirectional"))
    )
    (net (code "345") (name "unconnected-(IC3-PD23-PadH1)") (class "Default")
      (node (ref "IC3") (pin "H1") (pinfunction "PD23_H1") (pintype "bidirectional"))
    )
    (net (code "346") (name "unconnected-(IC3-PD24-PadJ3)") (class "Default")
      (node (ref "IC3") (pin "J3") (pinfunction "PD24_J3") (pintype "bidirectional"))
    )
    (net (code "347") (name "unconnected-(IC3-PD25-PadJ1)") (class "Default")
      (node (ref "IC3") (pin "J1") (pinfunction "PD25_J1") (pintype "bidirectional"))
    )
    (net (code "348") (name "unconnected-(IC3-PD26-PadJ4)") (class "Default")
      (node (ref "IC3") (pin "J4") (pinfunction "PD26_J4") (pintype "bidirectional"))
    )
    (net (code "349") (name "unconnected-(IC3-PD27-PadJ2)") (class "Default")
      (node (ref "IC3") (pin "J2") (pinfunction "PD27_J2") (pintype "bidirectional"))
    )
    (net (code "350") (name "unconnected-(SV1-Pad1)") (class "Default")
      (node (ref "SV1") (pin "1") (pinfunction "1_1") (pintype "passive"))
    )
    (net (code "351") (name "unconnected-(SV1-Pad2)") (class "Default")
      (node (ref "SV1") (pin "2") (pinfunction "2_2") (pintype "passive"))
    )
    (net (code "352") (name "unconnected-(SV1-Pad3)") (class "Default")
      (node (ref "SV1") (pin "3") (pinfunction "3_3") (pintype "passive"))
    )
    (net (code "353") (name "unconnected-(SV1-Pad4)") (class "Default")
      (node (ref "SV1") (pin "4") (pinfunction "4_4") (pintype "passive"))
    )
    (net (code "354") (name "unconnected-(SV1-Pad5)") (class "Default")
      (node (ref "SV1") (pin "5") (pinfunction "5_5") (pintype "passive"))
    )
    (net (code "355") (name "unconnected-(SV1-Pad6)") (class "Default")
      (node (ref "SV1") (pin "6") (pinfunction "6_6") (pintype "passive"))
    )
    (net (code "356") (name "unconnected-(SV1-Pad7)") (class "Default")
      (node (ref "SV1") (pin "7") (pinfunction "7_7") (pintype "passive"))
    )
    (net (code "357") (name "unconnected-(SV1-Pad8)") (class "Default")
      (node (ref "SV1") (pin "8") (pinfunction "8_8") (pintype "passive"))
    )
    (net (code "358") (name "unconnected-(SV1-Pad9)") (class "Default")
      (node (ref "SV1") (pin "9") (pinfunction "9_9") (pintype "passive"))
    )
    (net (code "359") (name "unconnected-(SV1-Pad10)") (class "Default")
      (node (ref "SV1") (pin "10") (pinfunction "10_10") (pintype "passive"))
    )
    (net (code "360") (name "unconnected-(SV1-Pad11)") (class "Default")
      (node (ref "SV1") (pin "11") (pinfunction "11_11") (pintype "passive"))
    )
    (net (code "361") (name "unconnected-(SV1-Pad12)") (class "Default")
      (node (ref "SV1") (pin "12") (pinfunction "12_12") (pintype "passive"))
    )
    (net (code "362") (name "unconnected-(SV1-Pad13)") (class "Default")
      (node (ref "SV1") (pin "13") (pinfunction "13_13") (pintype "passive"))
    )
    (net (code "363") (name "unconnected-(SV1-Pad14)") (class "Default")
      (node (ref "SV1") (pin "14") (pinfunction "14_14") (pintype "passive"))
    )
    (net (code "364") (name "unconnected-(SV1-Pad15)") (class "Default")
      (node (ref "SV1") (pin "15") (pinfunction "15_15") (pintype "passive"))
    )
    (net (code "365") (name "unconnected-(SV1-Pad16)") (class "Default")
      (node (ref "SV1") (pin "16") (pinfunction "16_16") (pintype "passive"))
    )
    (net (code "366") (name "unconnected-(SV1-Pad17)") (class "Default")
      (node (ref "SV1") (pin "17") (pinfunction "17_17") (pintype "passive"))
    )
    (net (code "367") (name "unconnected-(SV1-Pad18)") (class "Default")
      (node (ref "SV1") (pin "18") (pinfunction "18_18") (pintype "passive"))
    )
    (net (code "368") (name "unconnected-(SV1-Pad19)") (class "Default")
      (node (ref "SV1") (pin "19") (pinfunction "19_19") (pintype "passive"))
    )
    (net (code "369") (name "unconnected-(SV1-Pad20)") (class "Default")
      (node (ref "SV1") (pin "20") (pinfunction "20_20") (pintype "passive"))
    )
    (net (code "370") (name "unconnected-(SV1-Pad21)") (class "Default")
      (node (ref "SV1") (pin "21") (pinfunction "21_21") (pintype "passive"))
    )
    (net (code "371") (name "unconnected-(SV1-Pad22)") (class "Default")
      (node (ref "SV1") (pin "22") (pinfunction "22_22") (pintype "passive"))
    )
    (net (code "372") (name "unconnected-(SV1-Pad23)") (class "Default")
      (node (ref "SV1") (pin "23") (pinfunction "23_23") (pintype "passive"))
    )
    (net (code "373") (name "unconnected-(SV1-Pad24)") (class "Default")
      (node (ref "SV1") (pin "24") (pinfunction "24_24") (pintype "passive"))
    )
    (net (code "374") (name "unconnected-(SV1-Pad25)") (class "Default")
      (node (ref "SV1") (pin "25") (pinfunction "25_25") (pintype "passive"))
    )
    (net (code "375") (name "unconnected-(SV1-Pad26)") (class "Default")
      (node (ref "SV1") (pin "26") (pinfunction "26_26") (pintype "passive"))
    )
    (net (code "376") (name "unconnected-(SV1-Pad27)") (class "Default")
      (node (ref "SV1") (pin "27") (pinfunction "27_27") (pintype "passive"))
    )
    (net (code "377") (name "unconnected-(SV1-Pad28)") (class "Default")
      (node (ref "SV1") (pin "28") (pinfunction "28_28") (pintype "passive"))
    )
    (net (code "378") (name "unconnected-(SV1-Pad29)") (class "Default")
      (node (ref "SV1") (pin "29") (pinfunction "29_29") (pintype "passive"))
    )
    (net (code "379") (name "unconnected-(SV1-Pad30)") (class "Default")
      (node (ref "SV1") (pin "30") (pinfunction "30_30") (pintype "passive"))
    )
    (net (code "380") (name "unconnected-(SV1-Pad31)") (class "Default")
      (node (ref "SV1") (pin "31") (pinfunction "31_31") (pintype "passive"))
    )
    (net (code "381") (name "unconnected-(SV1-Pad32)") (class "Default")
      (node (ref "SV1") (pin "32") (pinfunction "32_32") (pintype "passive"))
    )
    (net (code "382") (name "unconnected-(SV1-Pad33)") (class "Default")
      (node (ref "SV1") (pin "33") (pinfunction "33_33") (pintype "passive"))
    )
    (net (code "383") (name "unconnected-(SV1-Pad34)") (class "Default")
      (node (ref "SV1") (pin "34") (pinfunction "34_34") (pintype "passive"))
    )
    (net (code "384") (name "unconnected-(SV1-Pad35)") (class "Default")
      (node (ref "SV1") (pin "35") (pinfunction "35_35") (pintype "passive"))
    )
    (net (code "385") (name "unconnected-(SV1-Pad36)") (class "Default")
      (node (ref "SV1") (pin "36") (pinfunction "36_36") (pintype "passive"))
    )
    (net (code "386") (name "unconnected-(U2-GND-Pad2)") (class "Default")
      (node (ref "U2") (pin "2") (pinfunction "GND_2") (pintype "bidirectional"))
    )
    (net (code "387") (name "unconnected-(U2-IO1-Pad1)") (class "Default")
      (node (ref "U2") (pin "1") (pinfunction "IO1_1") (pintype "bidirectional"))
    )
    (net (code "388") (name "unconnected-(U2-IO1-Pad6)") (class "Default")
      (node (ref "U2") (pin "6") (pinfunction "IO1_6") (pintype "bidirectional"))
    )
    (net (code "389") (name "unconnected-(U2-IO2-Pad3)") (class "Default")
      (node (ref "U2") (pin "3") (pinfunction "IO2_3") (pintype "bidirectional"))
    )
    (net (code "390") (name "unconnected-(U2-IO2-Pad4)") (class "Default")
      (node (ref "U2") (pin "4") (pinfunction "IO2_4") (pintype "bidirectional"))
    )
    (net (code "391") (name "unconnected-(U2-VBUS-Pad5)") (class "Default")
      (node (ref "U2") (pin "5") (pinfunction "VBUS_5") (pintype "bidirectional"))
    )
    (net (code "392") (name "unconnected-(X1-Pad1)") (class "Default")
      (node (ref "X1") (pin "1") (pinfunction "1_1") (pintype "passive"))
    )
    (net (code "393") (name "unconnected-(X1-Pad2)") (class "Default")
      (node (ref "X1") (pin "2") (pinfunction "2_2") (pintype "passive"))
    )
    (net (code "394") (name "unconnected-(X1-Pad3)") (class "Default")
      (node (ref "X1") (pin "3") (pinfunction "3_3") (pintype "passive"))
    )
    (net (code "395") (name "unconnected-(X1-Pad4)") (class "Default")
      (node (ref "X1") (pin "4") (pinfunction "4_4") (pintype "passive"))
    )
  )
)
